# coracao_8bits.net
KiCad netlist of a schematic drawn in EAGLE
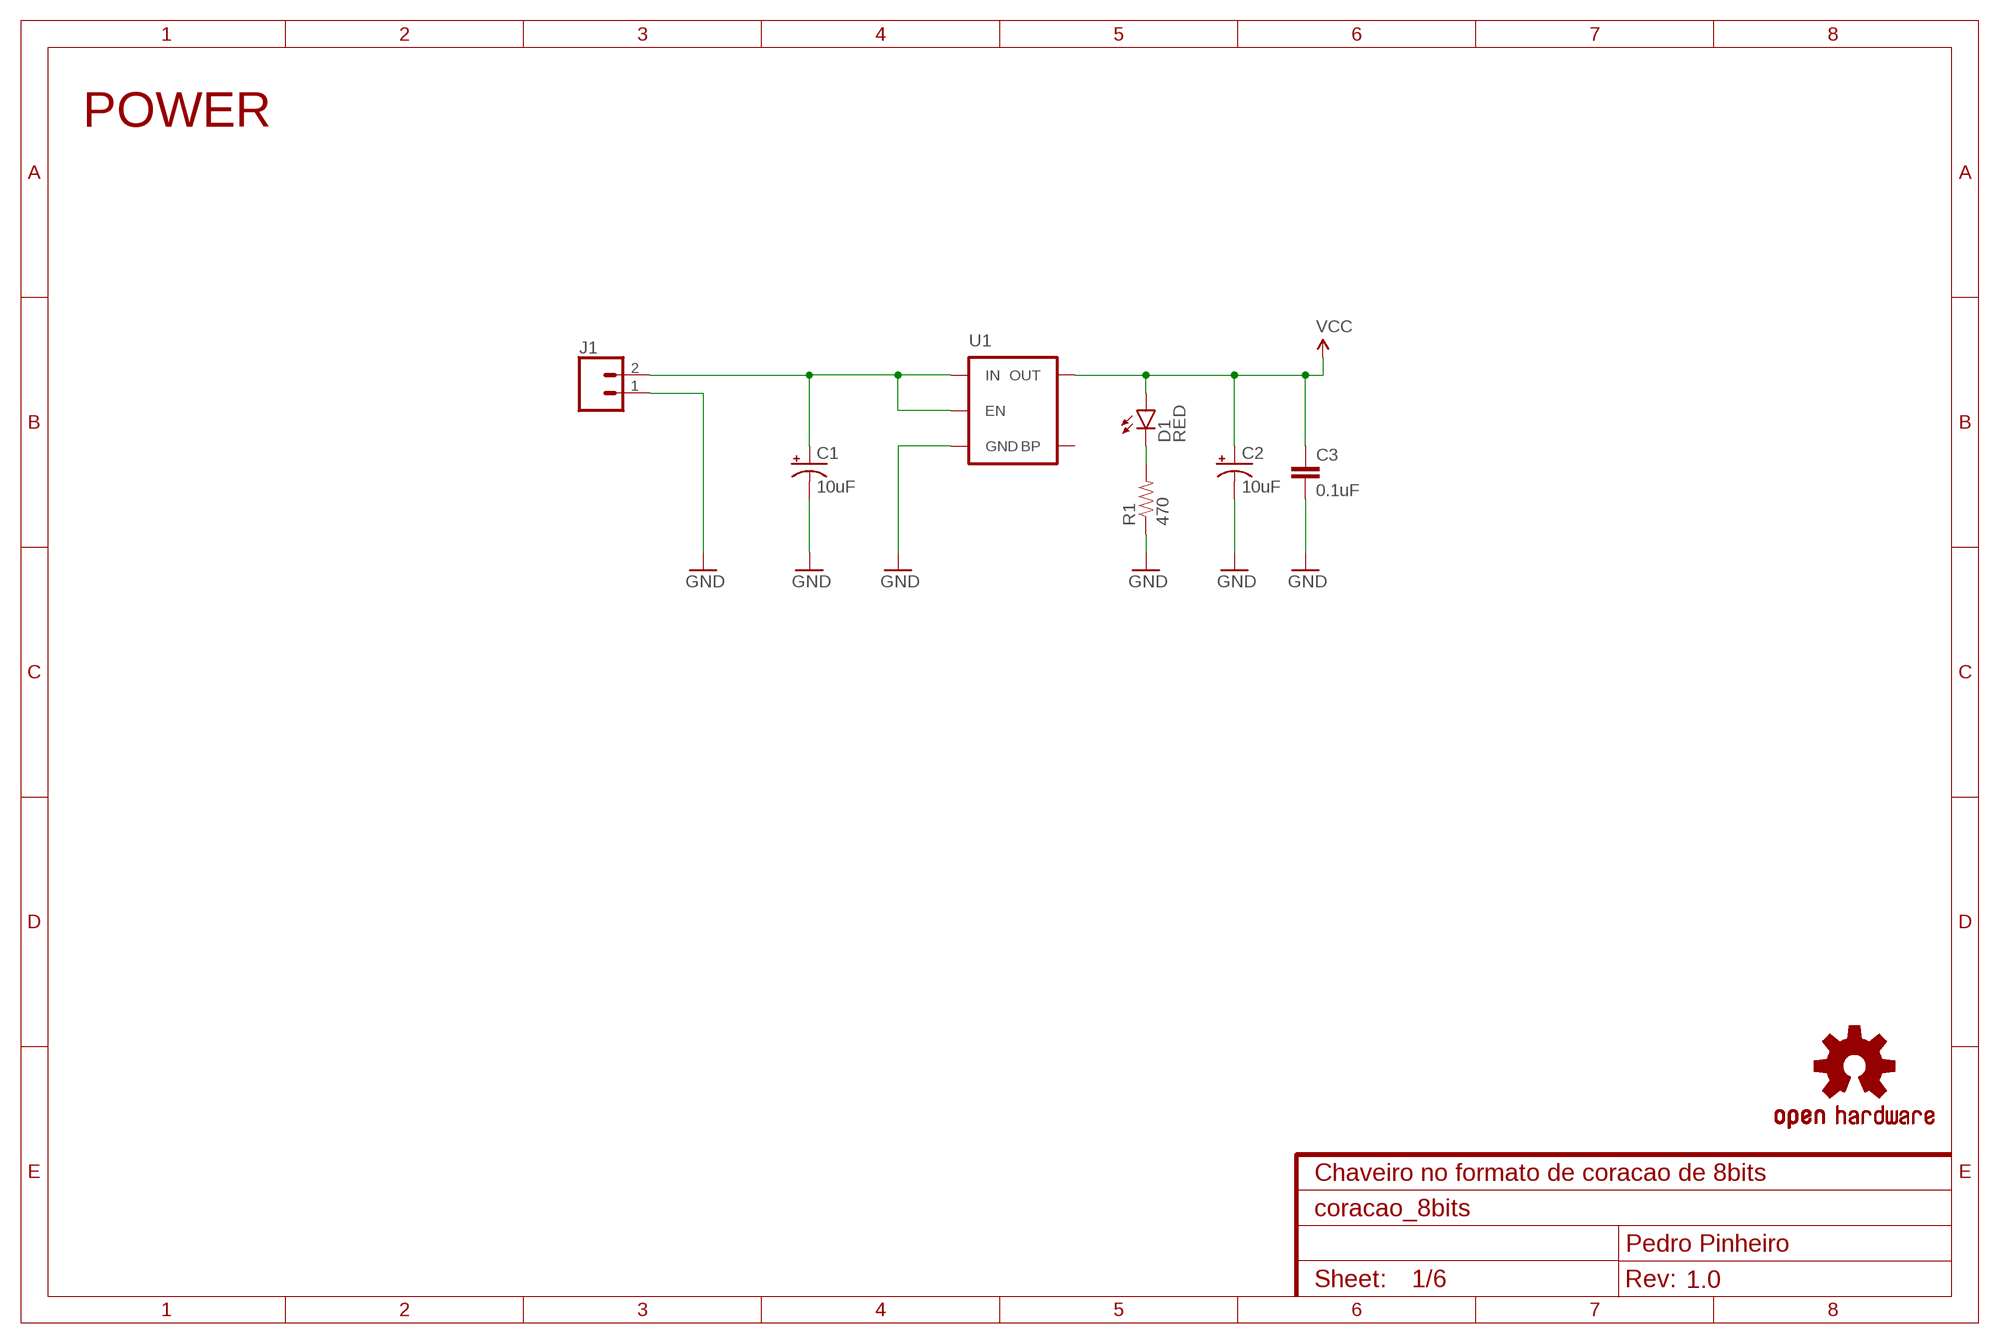
[diagram p0: schematic, sheet 1]
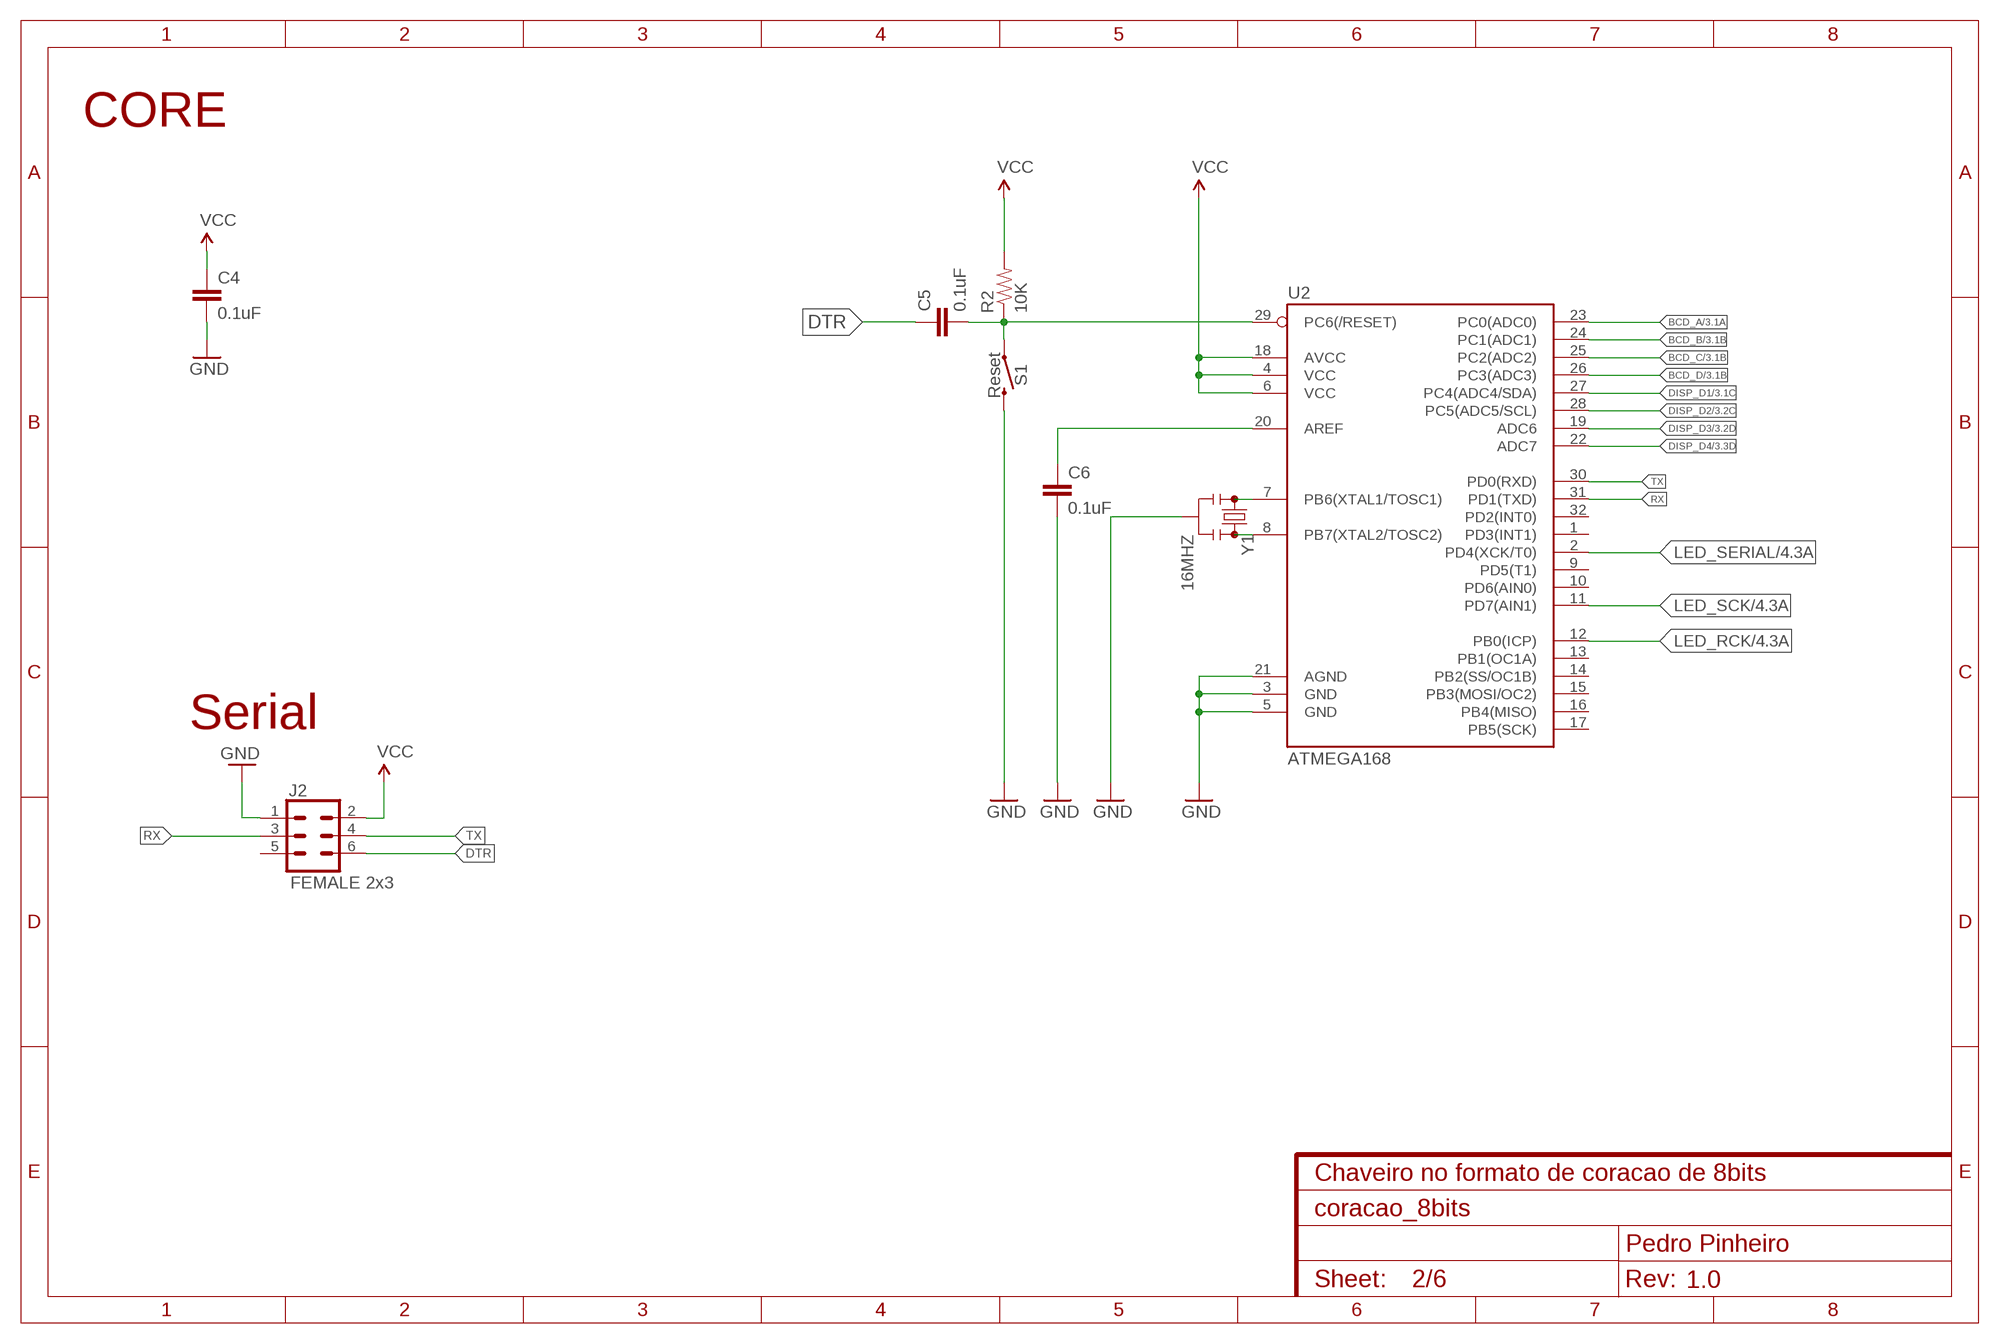
[diagram p1: schematic, sheet 2]
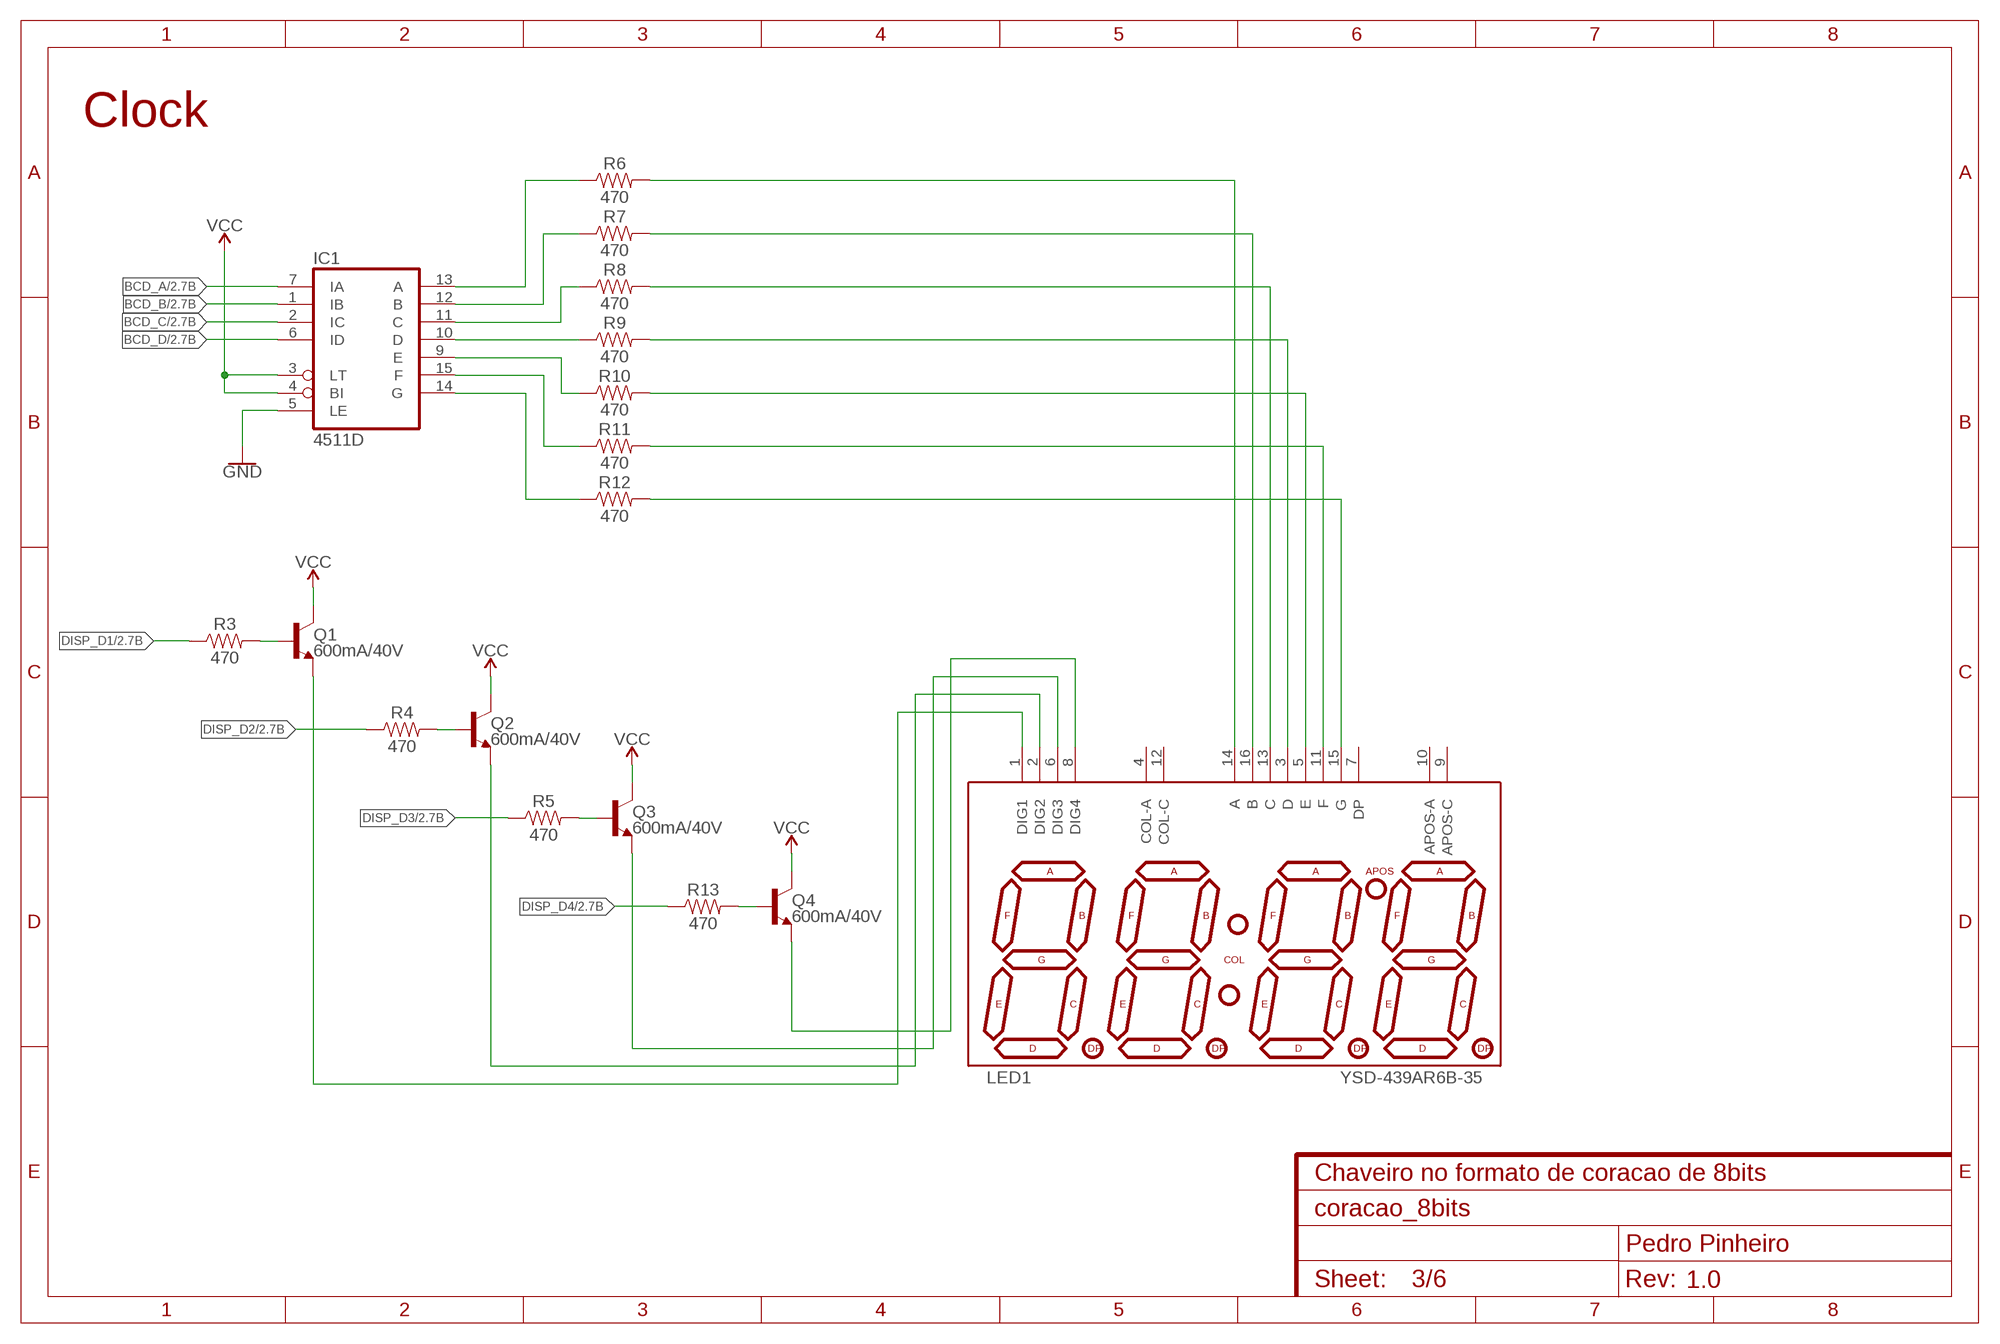
[diagram p2: schematic, sheet 3]
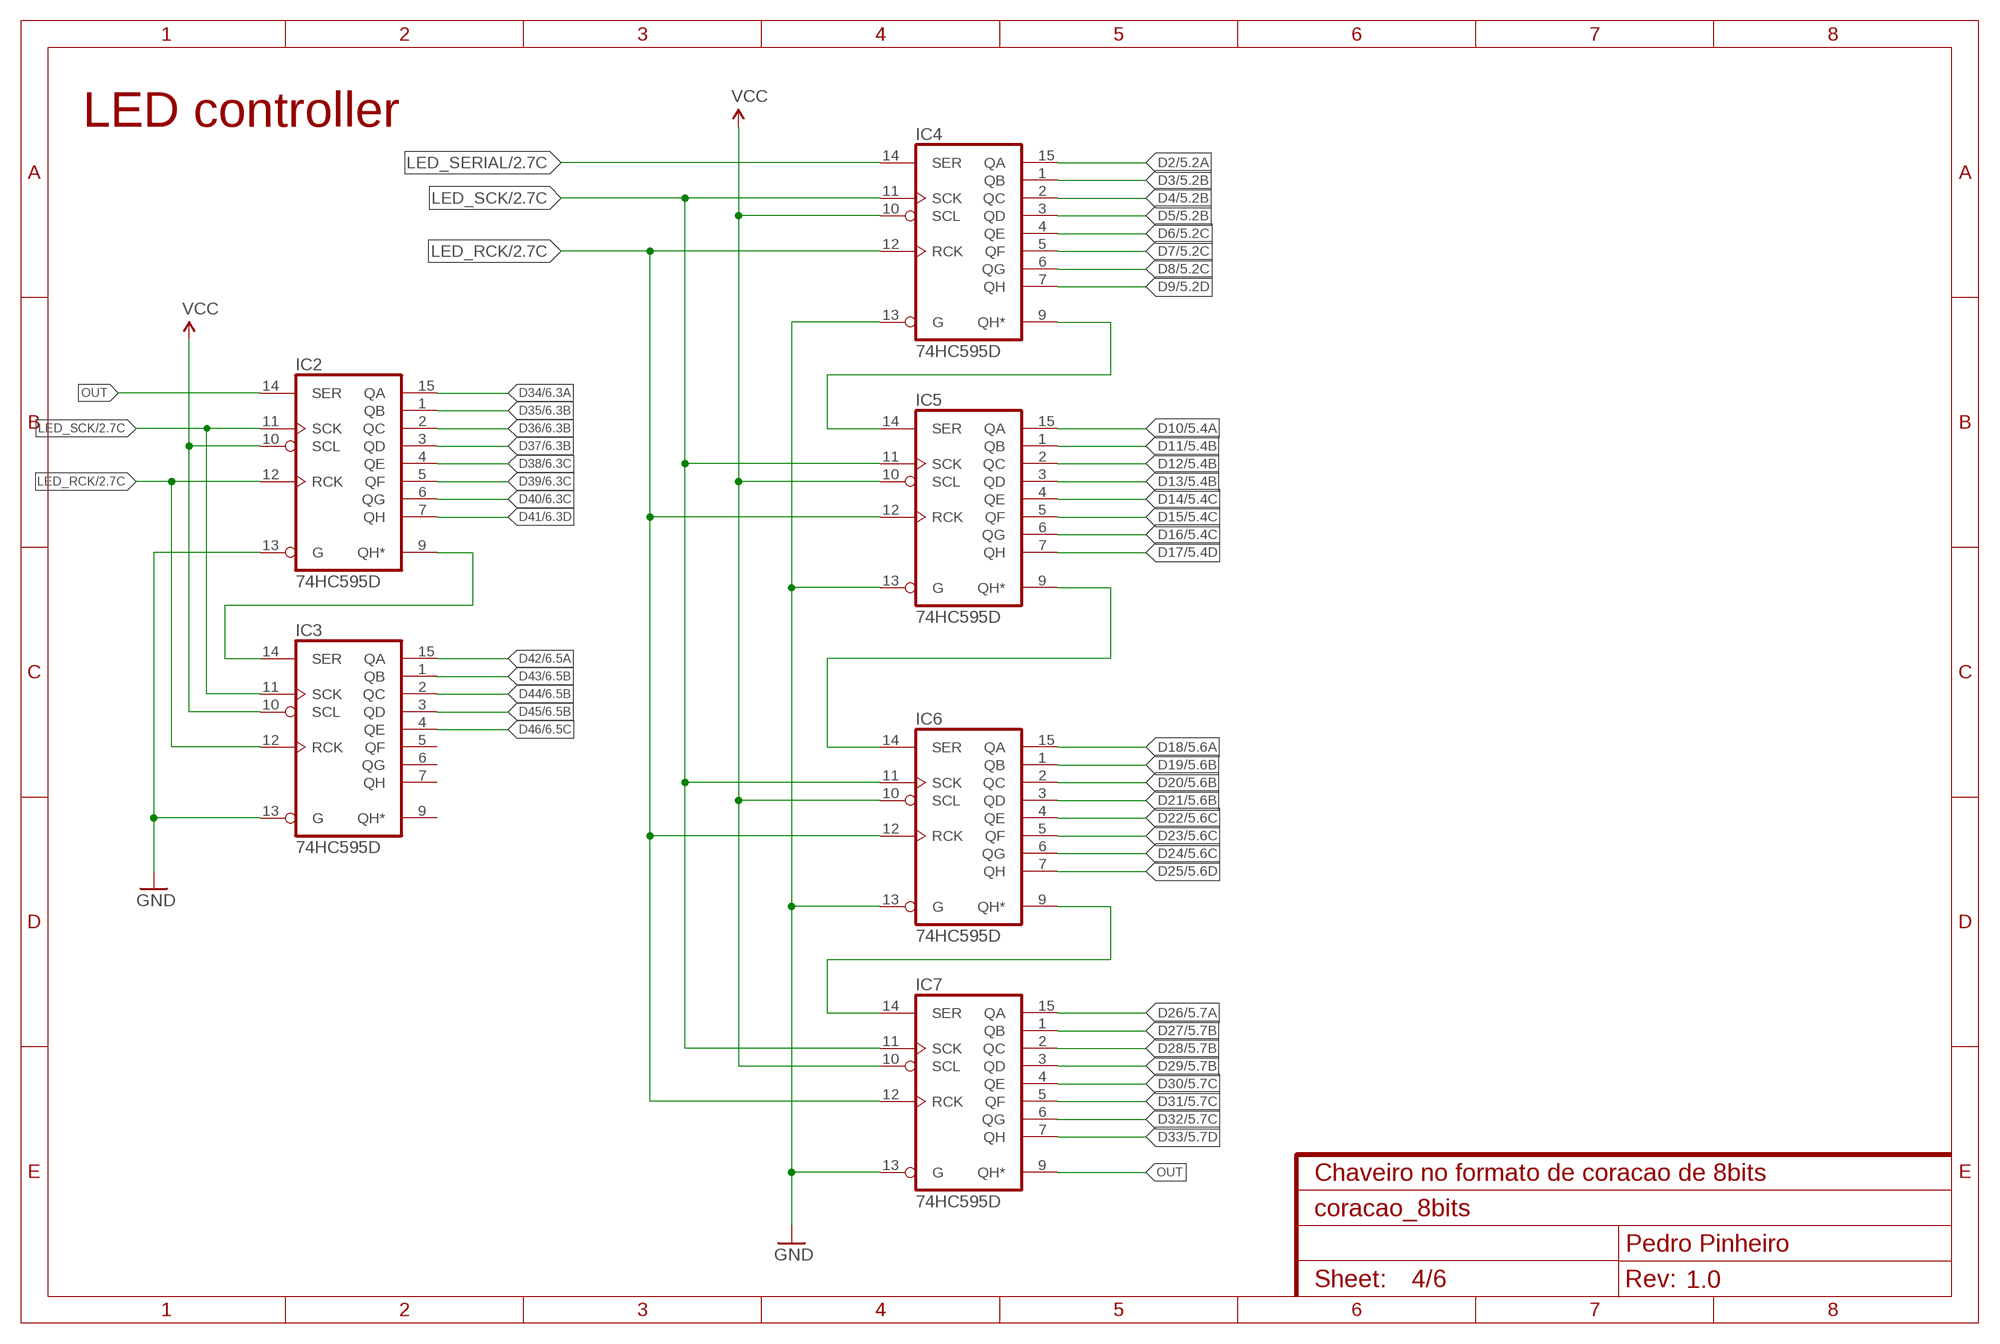
[diagram p3: schematic, sheet 4]
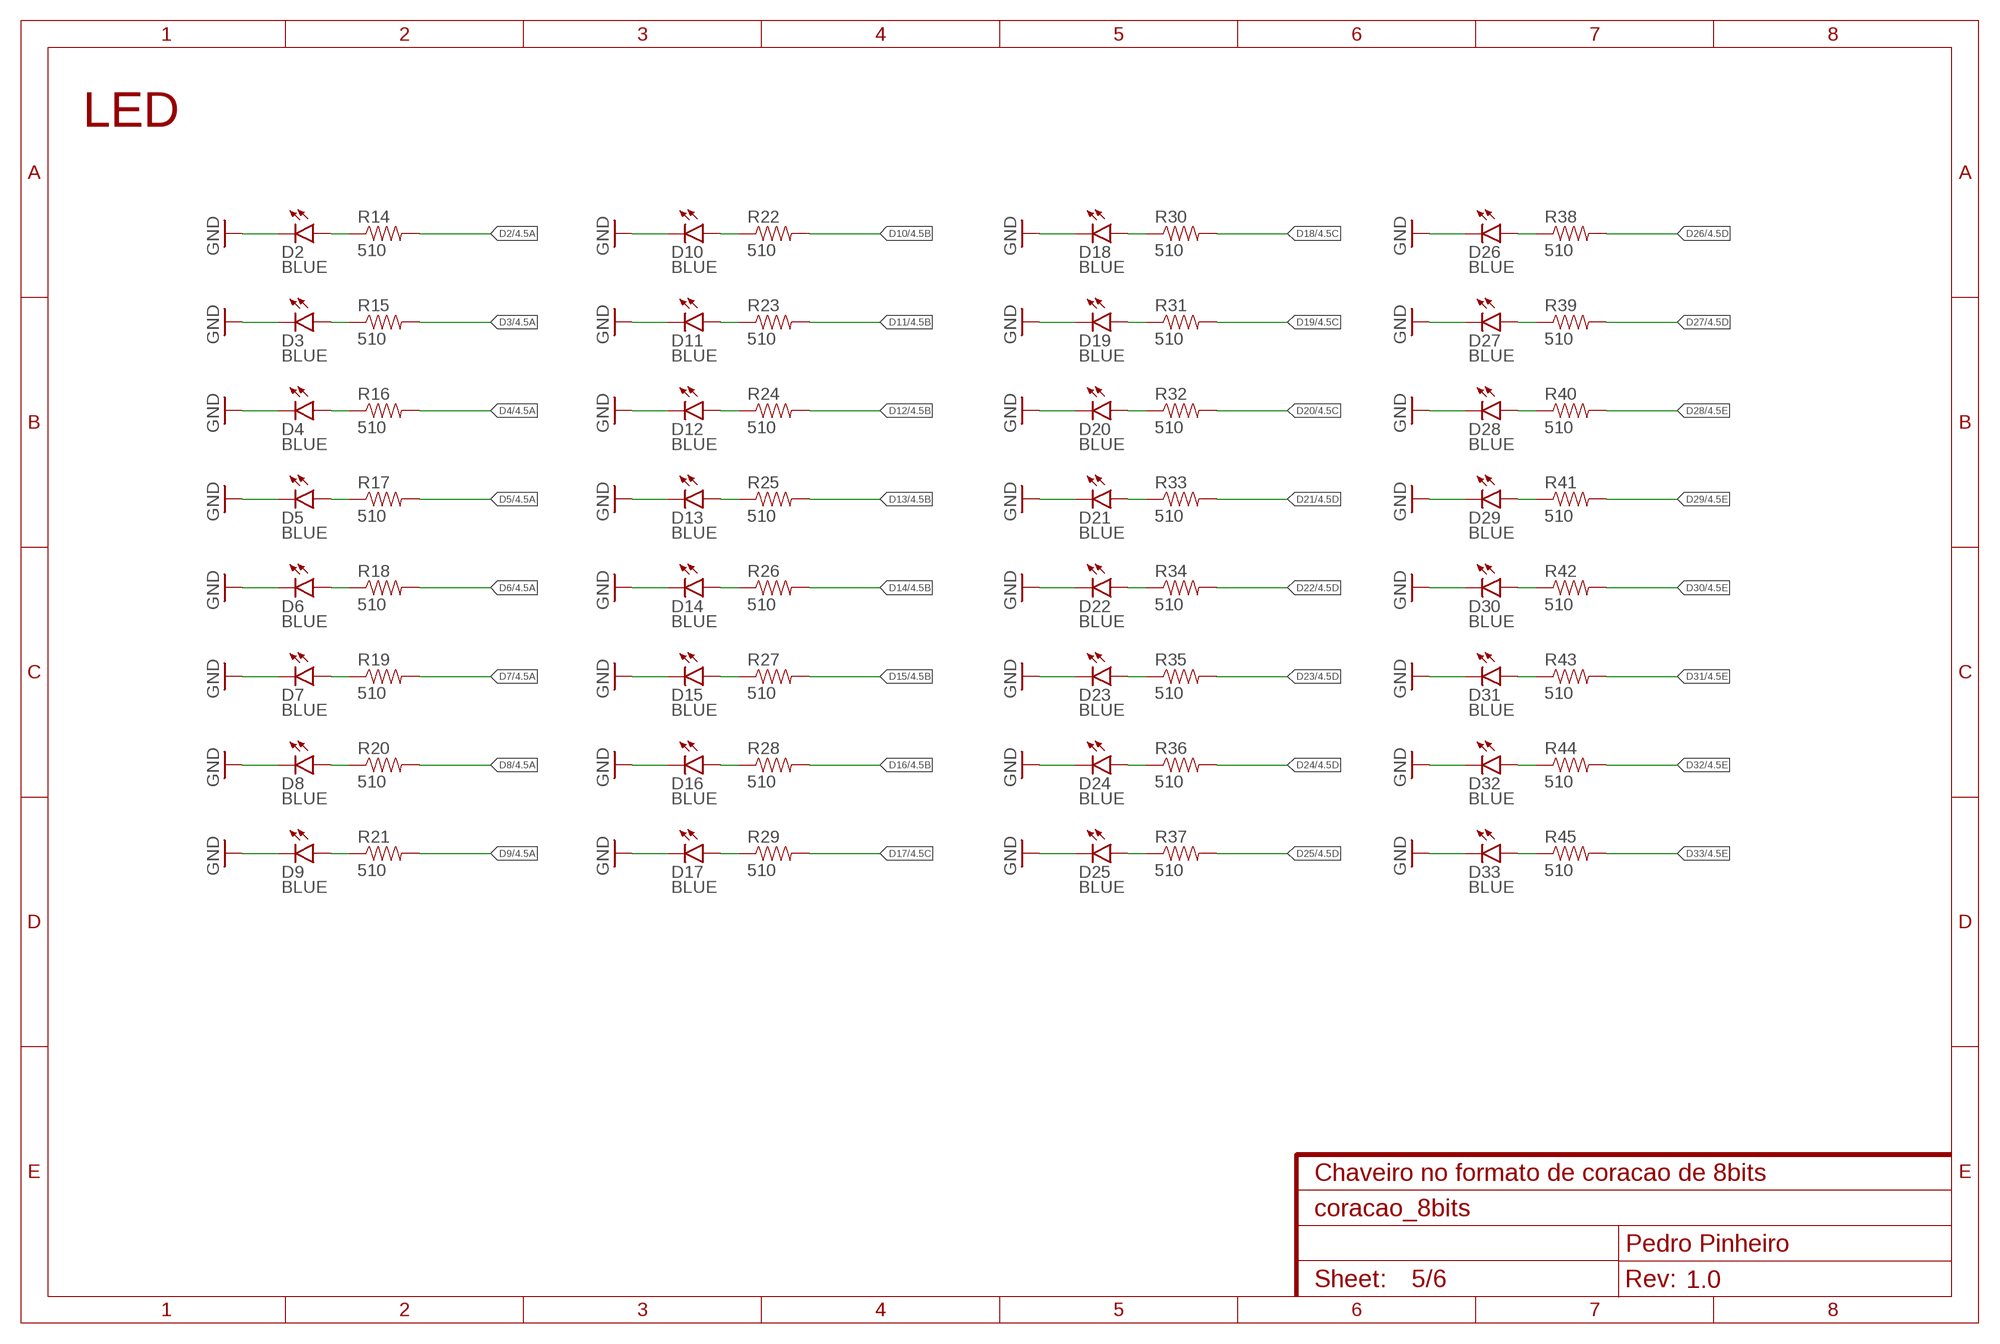
[diagram p4: schematic, sheet 5]
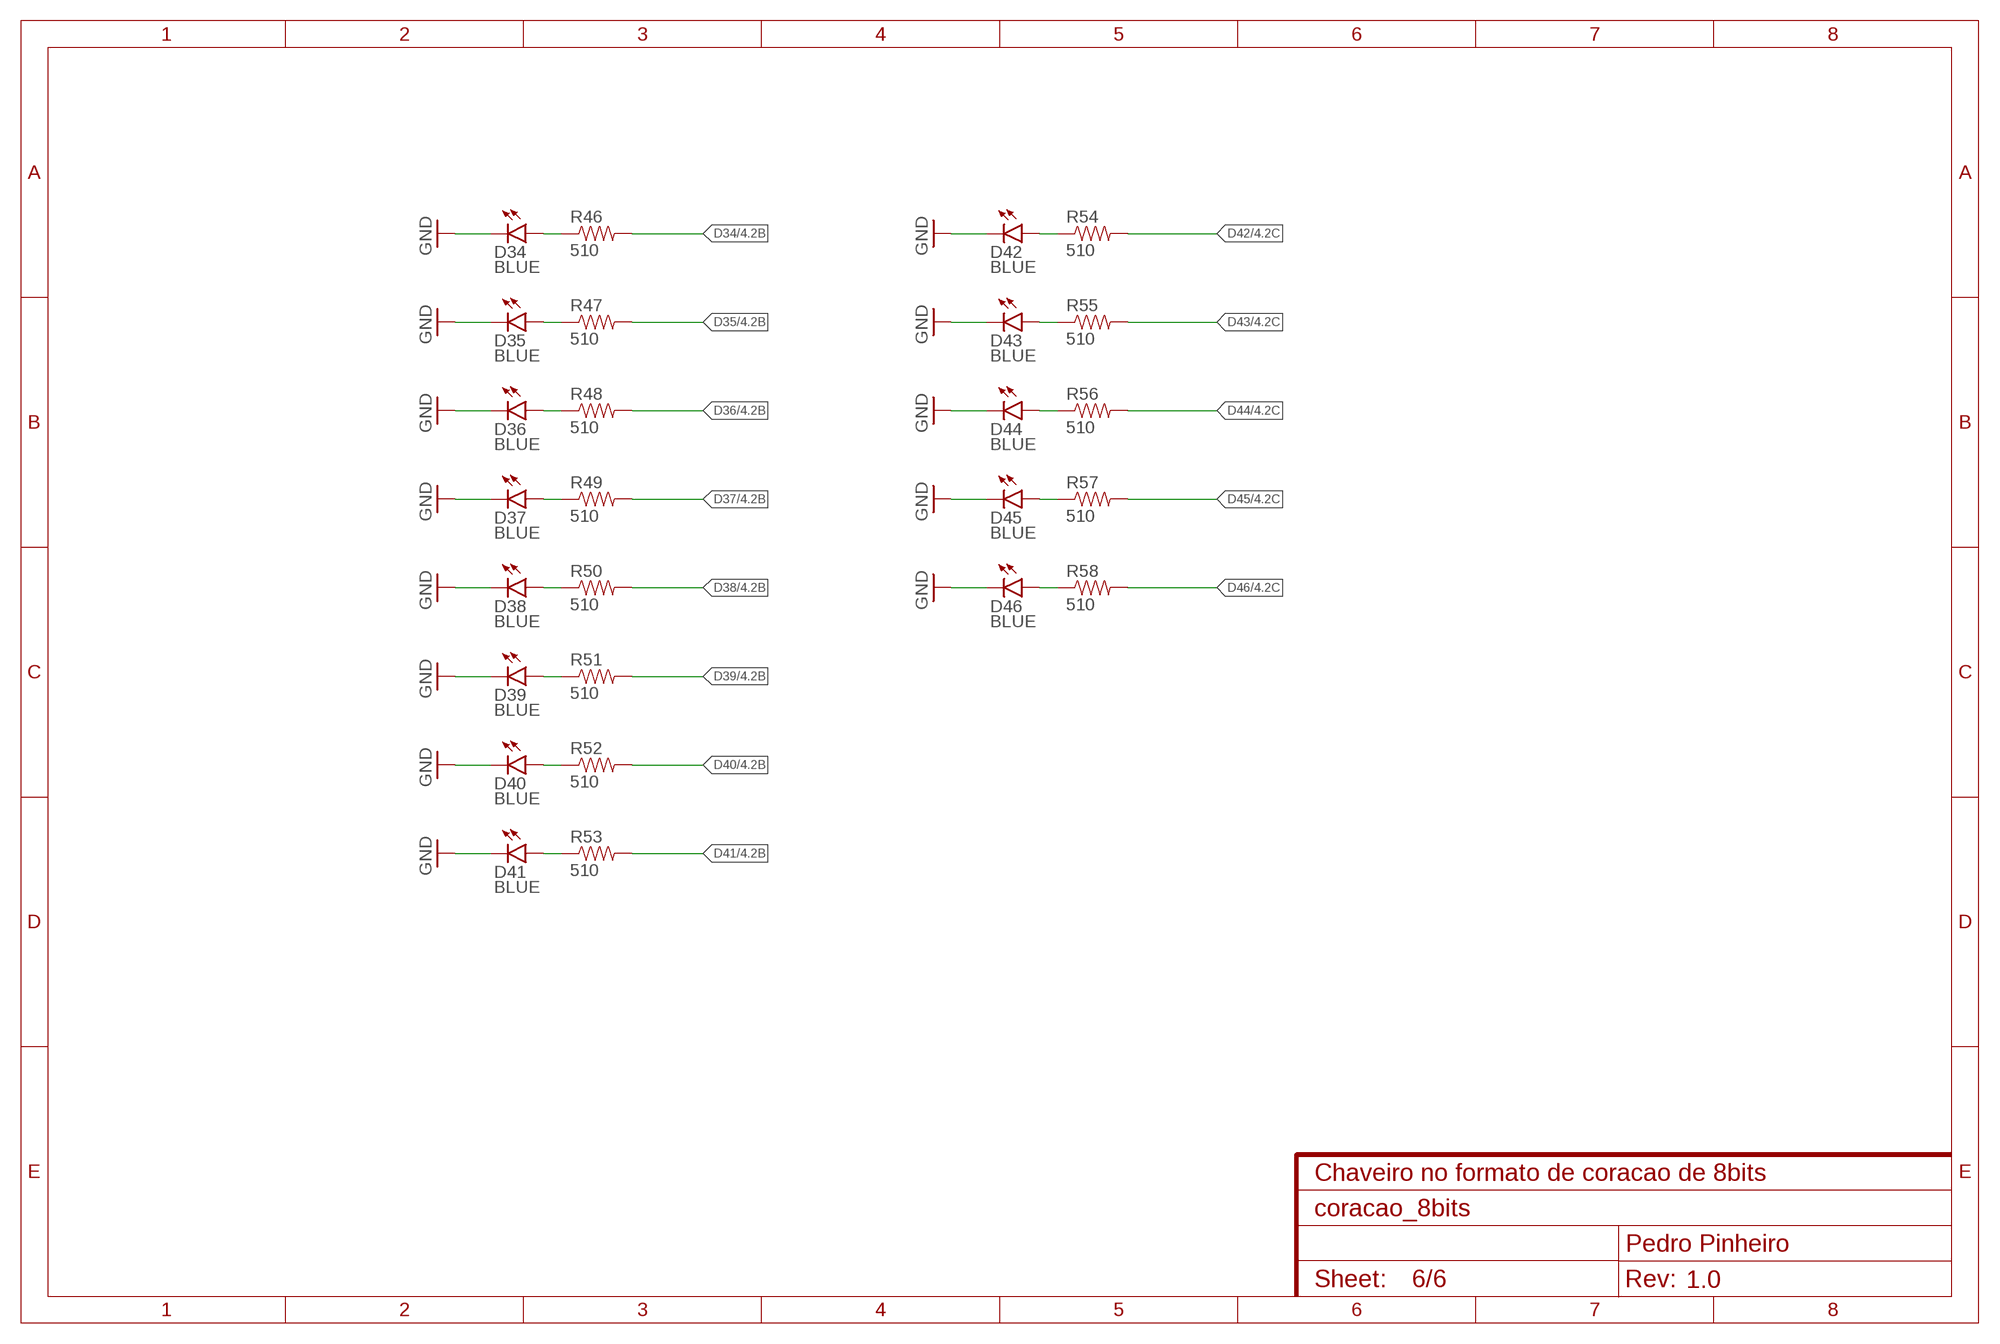
[diagram p5: schematic, sheet 6]

(export (version "E")
  (design (tool "Eeschema 10.0.6"))
  (components
    (comp (ref "IC2")
      (value "74HC595D")
      (footprint "eagle-import:SO16")
      (libsource (lib "eagle-import") (part "74595DHC"))
    )
    (comp (ref "IC3")
      (value "74HC595D")
      (footprint "eagle-import:SO16")
      (libsource (lib "eagle-import") (part "74595DHC"))
    )
    (comp (ref "IC4")
      (value "74HC595D")
      (footprint "eagle-import:SO16")
      (libsource (lib "eagle-import") (part "74595DHC"))
    )
    (comp (ref "IC5")
      (value "74HC595D")
      (footprint "eagle-import:SO16")
      (libsource (lib "eagle-import") (part "74595DHC"))
    )
    (comp (ref "IC6")
      (value "74HC595D")
      (footprint "eagle-import:SO16")
      (libsource (lib "eagle-import") (part "74595DHC"))
    )
    (comp (ref "IC7")
      (value "74HC595D")
      (footprint "eagle-import:SO16")
      (libsource (lib "eagle-import") (part "74595DHC"))
    )
    (comp (ref "C1")
      (value "10uF")
      (footprint "eagle-import:EIA3216")
      (libsource (lib "eagle-import") (part "CAP_POL1206"))
    )
    (comp (ref "C2")
      (value "10uF")
      (footprint "eagle-import:EIA3216")
      (libsource (lib "eagle-import") (part "CAP_POL1206"))
    )
    (comp (ref "C3")
      (value "0.1uF")
      (footprint "eagle-import:0603-CAP")
      (libsource (lib "eagle-import") (part "0.1UF-25V-5%(0603)"))
    )
    (comp (ref "D1")
      (value "RED")
      (footprint "eagle-import:LED-0603")
      (libsource (lib "eagle-import") (part "LED-RED0603"))
    )
    (comp (ref "J1")
      (value "CONN_02")
      (footprint "eagle-import:1X02")
      (libsource (lib "eagle-import") (part "CONN_02"))
    )
    (comp (ref "LOGO1")
      (value "OSHW-LOGOMINI")
      (footprint "eagle-import:OSHW-LOGO-MINI")
      (libsource (lib "eagle-import") (part "OSHW-LOGOMINI"))
    )
    (comp (ref "R1")
      (value "470")
      (footprint "eagle-import:0603-RES")
      (libsource (lib "eagle-import") (part "470OHM1/10W1%(0603)"))
    )
    (comp (ref "U1")
      (value "MIC52053.3V")
      (footprint "eagle-import:SOT23-5")
      (libsource (lib "eagle-import") (part "MIC52053.3V"))
    )
    (comp (ref "IC1")
      (value "4511D")
      (footprint "eagle-import:SO16")
      (libsource (lib "eagle-import") (part "4511D"))
    )
    (comp (ref "LED1")
      (value "YSD-439AR6B-35")
      (footprint "eagle-import:7-SEGMENT-4DIGIT-YOUNGSUN")
      (libsource (lib "eagle-import") (part "7-SEGMENT-4DIGIT-10MM-RED"))
    )
    (comp (ref "Q1")
      (value "600mA/40V")
      (footprint "eagle-import:SOT23-3")
      (libsource (lib "eagle-import") (part "TRANS_NPN-MMBT2222AL"))
    )
    (comp (ref "Q2")
      (value "600mA/40V")
      (footprint "eagle-import:SOT23-3")
      (libsource (lib "eagle-import") (part "TRANS_NPN-MMBT2222AL"))
    )
    (comp (ref "Q3")
      (value "600mA/40V")
      (footprint "eagle-import:SOT23-3")
      (libsource (lib "eagle-import") (part "TRANS_NPN-MMBT2222AL"))
    )
    (comp (ref "Q4")
      (value "600mA/40V")
      (footprint "eagle-import:SOT23-3")
      (libsource (lib "eagle-import") (part "TRANS_NPN-MMBT2222AL"))
    )
    (comp (ref "R3")
      (value "470")
      (footprint "eagle-import:0603")
      (libsource (lib "eagle-import") (part "470OHM-0603-1/10W-1%"))
    )
    (comp (ref "R4")
      (value "470")
      (footprint "eagle-import:0603")
      (libsource (lib "eagle-import") (part "470OHM-0603-1/10W-1%"))
    )
    (comp (ref "R5")
      (value "470")
      (footprint "eagle-import:0603")
      (libsource (lib "eagle-import") (part "470OHM-0603-1/10W-1%"))
    )
    (comp (ref "R6")
      (value "470")
      (footprint "eagle-import:0603")
      (libsource (lib "eagle-import") (part "470OHM-0603-1/10W-1%"))
    )
    (comp (ref "R7")
      (value "470")
      (footprint "eagle-import:0603")
      (libsource (lib "eagle-import") (part "470OHM-0603-1/10W-1%"))
    )
    (comp (ref "R8")
      (value "470")
      (footprint "eagle-import:0603")
      (libsource (lib "eagle-import") (part "470OHM-0603-1/10W-1%"))
    )
    (comp (ref "R9")
      (value "470")
      (footprint "eagle-import:0603")
      (libsource (lib "eagle-import") (part "470OHM-0603-1/10W-1%"))
    )
    (comp (ref "R10")
      (value "470")
      (footprint "eagle-import:0603")
      (libsource (lib "eagle-import") (part "470OHM-0603-1/10W-1%"))
    )
    (comp (ref "R11")
      (value "470")
      (footprint "eagle-import:0603")
      (libsource (lib "eagle-import") (part "470OHM-0603-1/10W-1%"))
    )
    (comp (ref "R12")
      (value "470")
      (footprint "eagle-import:0603")
      (libsource (lib "eagle-import") (part "470OHM-0603-1/10W-1%"))
    )
    (comp (ref "R13")
      (value "470")
      (footprint "eagle-import:0603")
      (libsource (lib "eagle-import") (part "470OHM-0603-1/10W-1%"))
    )
    (comp (ref "C4")
      (value "0.1uF")
      (footprint "eagle-import:0603-CAP")
      (libsource (lib "eagle-import") (part "0.1UF-100V-10%(0603)"))
    )
    (comp (ref "C5")
      (value "0.1uF")
      (footprint "eagle-import:0603-CAP")
      (libsource (lib "eagle-import") (part "0.1UF-100V-10%(0603)"))
    )
    (comp (ref "C6")
      (value "0.1uF")
      (footprint "eagle-import:0603-CAP")
      (libsource (lib "eagle-import") (part "0.1UF-100V-10%(0603)"))
    )
    (comp (ref "J2")
      (value "FEMALE 2x3")
      (footprint "eagle-import:2X3")
      (libsource (lib "eagle-import") (part "CONN_03X2FEMALE"))
    )
    (comp (ref "R2")
      (value "10K")
      (footprint "eagle-import:0603-RES")
      (libsource (lib "eagle-import") (part "10KOHM-1/10W-1%(0603)0603"))
    )
    (comp (ref "S1")
      (value "Reset")
      (footprint "eagle-import:TACTILE_SWITCH_SMD_6.0X3.5MM")
      (libsource (lib "eagle-import") (part "MOMENTARY-SWITCH-SPST-SMD-6.0X3.5MM"))
    )
    (comp (ref "U2")
      (value "ATMEGA168")
      (footprint "eagle-import:TQFP32-08")
      (libsource (lib "eagle-import") (part "ATMEGA168"))
    )
    (comp (ref "Y1")
      (value "16MHZ")
      (footprint "eagle-import:RESONATOR-SMD")
      (libsource (lib "eagle-import") (part "RESONATOR16MHZ"))
    )
    (comp (ref "D34")
      (value "BLUE")
      (footprint "eagle-import:LED-0603")
      (libsource (lib "eagle-import") (part "LED-BLUE0603"))
    )
    (comp (ref "D35")
      (value "BLUE")
      (footprint "eagle-import:LED-0603")
      (libsource (lib "eagle-import") (part "LED-BLUE0603"))
    )
    (comp (ref "D36")
      (value "BLUE")
      (footprint "eagle-import:LED-0603")
      (libsource (lib "eagle-import") (part "LED-BLUE0603"))
    )
    (comp (ref "D37")
      (value "BLUE")
      (footprint "eagle-import:LED-0603")
      (libsource (lib "eagle-import") (part "LED-BLUE0603"))
    )
    (comp (ref "D38")
      (value "BLUE")
      (footprint "eagle-import:LED-0603")
      (libsource (lib "eagle-import") (part "LED-BLUE0603"))
    )
    (comp (ref "D39")
      (value "BLUE")
      (footprint "eagle-import:LED-0603")
      (libsource (lib "eagle-import") (part "LED-BLUE0603"))
    )
    (comp (ref "D40")
      (value "BLUE")
      (footprint "eagle-import:LED-0603")
      (libsource (lib "eagle-import") (part "LED-BLUE0603"))
    )
    (comp (ref "D41")
      (value "BLUE")
      (footprint "eagle-import:LED-0603")
      (libsource (lib "eagle-import") (part "LED-BLUE0603"))
    )
    (comp (ref "D42")
      (value "BLUE")
      (footprint "eagle-import:LED-0603")
      (libsource (lib "eagle-import") (part "LED-BLUE0603"))
    )
    (comp (ref "D43")
      (value "BLUE")
      (footprint "eagle-import:LED-0603")
      (libsource (lib "eagle-import") (part "LED-BLUE0603"))
    )
    (comp (ref "D44")
      (value "BLUE")
      (footprint "eagle-import:LED-0603")
      (libsource (lib "eagle-import") (part "LED-BLUE0603"))
    )
    (comp (ref "D45")
      (value "BLUE")
      (footprint "eagle-import:LED-0603")
      (libsource (lib "eagle-import") (part "LED-BLUE0603"))
    )
    (comp (ref "D46")
      (value "BLUE")
      (footprint "eagle-import:LED-0603")
      (libsource (lib "eagle-import") (part "LED-BLUE0603"))
    )
    (comp (ref "R46")
      (value "510")
      (footprint "eagle-import:0603-RES")
      (libsource (lib "eagle-import") (part "470OHM1/10W1%(0603)"))
    )
    (comp (ref "R47")
      (value "510")
      (footprint "eagle-import:0603-RES")
      (libsource (lib "eagle-import") (part "470OHM1/10W1%(0603)"))
    )
    (comp (ref "R48")
      (value "510")
      (footprint "eagle-import:0603-RES")
      (libsource (lib "eagle-import") (part "470OHM1/10W1%(0603)"))
    )
    (comp (ref "R49")
      (value "510")
      (footprint "eagle-import:0603-RES")
      (libsource (lib "eagle-import") (part "470OHM1/10W1%(0603)"))
    )
    (comp (ref "R50")
      (value "510")
      (footprint "eagle-import:0603-RES")
      (libsource (lib "eagle-import") (part "470OHM1/10W1%(0603)"))
    )
    (comp (ref "R51")
      (value "510")
      (footprint "eagle-import:0603-RES")
      (libsource (lib "eagle-import") (part "470OHM1/10W1%(0603)"))
    )
    (comp (ref "R52")
      (value "510")
      (footprint "eagle-import:0603-RES")
      (libsource (lib "eagle-import") (part "470OHM1/10W1%(0603)"))
    )
    (comp (ref "R53")
      (value "510")
      (footprint "eagle-import:0603-RES")
      (libsource (lib "eagle-import") (part "470OHM1/10W1%(0603)"))
    )
    (comp (ref "R54")
      (value "510")
      (footprint "eagle-import:0603-RES")
      (libsource (lib "eagle-import") (part "470OHM1/10W1%(0603)"))
    )
    (comp (ref "R55")
      (value "510")
      (footprint "eagle-import:0603-RES")
      (libsource (lib "eagle-import") (part "470OHM1/10W1%(0603)"))
    )
    (comp (ref "R56")
      (value "510")
      (footprint "eagle-import:0603-RES")
      (libsource (lib "eagle-import") (part "470OHM1/10W1%(0603)"))
    )
    (comp (ref "R57")
      (value "510")
      (footprint "eagle-import:0603-RES")
      (libsource (lib "eagle-import") (part "470OHM1/10W1%(0603)"))
    )
    (comp (ref "R58")
      (value "510")
      (footprint "eagle-import:0603-RES")
      (libsource (lib "eagle-import") (part "470OHM1/10W1%(0603)"))
    )
    (comp (ref "D2")
      (value "BLUE")
      (footprint "eagle-import:LED-0603")
      (libsource (lib "eagle-import") (part "LED-BLUE0603"))
    )
    (comp (ref "D3")
      (value "BLUE")
      (footprint "eagle-import:LED-0603")
      (libsource (lib "eagle-import") (part "LED-BLUE0603"))
    )
    (comp (ref "D4")
      (value "BLUE")
      (footprint "eagle-import:LED-0603")
      (libsource (lib "eagle-import") (part "LED-BLUE0603"))
    )
    (comp (ref "D5")
      (value "BLUE")
      (footprint "eagle-import:LED-0603")
      (libsource (lib "eagle-import") (part "LED-BLUE0603"))
    )
    (comp (ref "D6")
      (value "BLUE")
      (footprint "eagle-import:LED-0603")
      (libsource (lib "eagle-import") (part "LED-BLUE0603"))
    )
    (comp (ref "D7")
      (value "BLUE")
      (footprint "eagle-import:LED-0603")
      (libsource (lib "eagle-import") (part "LED-BLUE0603"))
    )
    (comp (ref "D8")
      (value "BLUE")
      (footprint "eagle-import:LED-0603")
      (libsource (lib "eagle-import") (part "LED-BLUE0603"))
    )
    (comp (ref "D9")
      (value "BLUE")
      (footprint "eagle-import:LED-0603")
      (libsource (lib "eagle-import") (part "LED-BLUE0603"))
    )
    (comp (ref "D10")
      (value "BLUE")
      (footprint "eagle-import:LED-0603")
      (libsource (lib "eagle-import") (part "LED-BLUE0603"))
    )
    (comp (ref "D11")
      (value "BLUE")
      (footprint "eagle-import:LED-0603")
      (libsource (lib "eagle-import") (part "LED-BLUE0603"))
    )
    (comp (ref "D12")
      (value "BLUE")
      (footprint "eagle-import:LED-0603")
      (libsource (lib "eagle-import") (part "LED-BLUE0603"))
    )
    (comp (ref "D13")
      (value "BLUE")
      (footprint "eagle-import:LED-0603")
      (libsource (lib "eagle-import") (part "LED-BLUE0603"))
    )
    (comp (ref "D14")
      (value "BLUE")
      (footprint "eagle-import:LED-0603")
      (libsource (lib "eagle-import") (part "LED-BLUE0603"))
    )
    (comp (ref "D15")
      (value "BLUE")
      (footprint "eagle-import:LED-0603")
      (libsource (lib "eagle-import") (part "LED-BLUE0603"))
    )
    (comp (ref "D16")
      (value "BLUE")
      (footprint "eagle-import:LED-0603")
      (libsource (lib "eagle-import") (part "LED-BLUE0603"))
    )
    (comp (ref "D17")
      (value "BLUE")
      (footprint "eagle-import:LED-0603")
      (libsource (lib "eagle-import") (part "LED-BLUE0603"))
    )
    (comp (ref "D18")
      (value "BLUE")
      (footprint "eagle-import:LED-0603")
      (libsource (lib "eagle-import") (part "LED-BLUE0603"))
    )
    (comp (ref "D19")
      (value "BLUE")
      (footprint "eagle-import:LED-0603")
      (libsource (lib "eagle-import") (part "LED-BLUE0603"))
    )
    (comp (ref "D20")
      (value "BLUE")
      (footprint "eagle-import:LED-0603")
      (libsource (lib "eagle-import") (part "LED-BLUE0603"))
    )
    (comp (ref "D21")
      (value "BLUE")
      (footprint "eagle-import:LED-0603")
      (libsource (lib "eagle-import") (part "LED-BLUE0603"))
    )
    (comp (ref "D22")
      (value "BLUE")
      (footprint "eagle-import:LED-0603")
      (libsource (lib "eagle-import") (part "LED-BLUE0603"))
    )
    (comp (ref "D23")
      (value "BLUE")
      (footprint "eagle-import:LED-0603")
      (libsource (lib "eagle-import") (part "LED-BLUE0603"))
    )
    (comp (ref "D24")
      (value "BLUE")
      (footprint "eagle-import:LED-0603")
      (libsource (lib "eagle-import") (part "LED-BLUE0603"))
    )
    (comp (ref "D25")
      (value "BLUE")
      (footprint "eagle-import:LED-0603")
      (libsource (lib "eagle-import") (part "LED-BLUE0603"))
    )
    (comp (ref "D26")
      (value "BLUE")
      (footprint "eagle-import:LED-0603")
      (libsource (lib "eagle-import") (part "LED-BLUE0603"))
    )
    (comp (ref "D27")
      (value "BLUE")
      (footprint "eagle-import:LED-0603")
      (libsource (lib "eagle-import") (part "LED-BLUE0603"))
    )
    (comp (ref "D28")
      (value "BLUE")
      (footprint "eagle-import:LED-0603")
      (libsource (lib "eagle-import") (part "LED-BLUE0603"))
    )
    (comp (ref "D29")
      (value "BLUE")
      (footprint "eagle-import:LED-0603")
      (libsource (lib "eagle-import") (part "LED-BLUE0603"))
    )
    (comp (ref "D30")
      (value "BLUE")
      (footprint "eagle-import:LED-0603")
      (libsource (lib "eagle-import") (part "LED-BLUE0603"))
    )
    (comp (ref "D31")
      (value "BLUE")
      (footprint "eagle-import:LED-0603")
      (libsource (lib "eagle-import") (part "LED-BLUE0603"))
    )
    (comp (ref "D32")
      (value "BLUE")
      (footprint "eagle-import:LED-0603")
      (libsource (lib "eagle-import") (part "LED-BLUE0603"))
    )
    (comp (ref "D33")
      (value "BLUE")
      (footprint "eagle-import:LED-0603")
      (libsource (lib "eagle-import") (part "LED-BLUE0603"))
    )
    (comp (ref "R14")
      (value "510")
      (footprint "eagle-import:0603-RES")
      (libsource (lib "eagle-import") (part "470OHM1/10W1%(0603)"))
    )
    (comp (ref "R15")
      (value "510")
      (footprint "eagle-import:0603-RES")
      (libsource (lib "eagle-import") (part "470OHM1/10W1%(0603)"))
    )
    (comp (ref "R16")
      (value "510")
      (footprint "eagle-import:0603-RES")
      (libsource (lib "eagle-import") (part "470OHM1/10W1%(0603)"))
    )
    (comp (ref "R17")
      (value "510")
      (footprint "eagle-import:0603-RES")
      (libsource (lib "eagle-import") (part "470OHM1/10W1%(0603)"))
    )
    (comp (ref "R18")
      (value "510")
      (footprint "eagle-import:0603-RES")
      (libsource (lib "eagle-import") (part "470OHM1/10W1%(0603)"))
    )
    (comp (ref "R19")
      (value "510")
      (footprint "eagle-import:0603-RES")
      (libsource (lib "eagle-import") (part "470OHM1/10W1%(0603)"))
    )
    (comp (ref "R20")
      (value "510")
      (footprint "eagle-import:0603-RES")
      (libsource (lib "eagle-import") (part "470OHM1/10W1%(0603)"))
    )
    (comp (ref "R21")
      (value "510")
      (footprint "eagle-import:0603-RES")
      (libsource (lib "eagle-import") (part "470OHM1/10W1%(0603)"))
    )
    (comp (ref "R22")
      (value "510")
      (footprint "eagle-import:0603-RES")
      (libsource (lib "eagle-import") (part "470OHM1/10W1%(0603)"))
    )
    (comp (ref "R23")
      (value "510")
      (footprint "eagle-import:0603-RES")
      (libsource (lib "eagle-import") (part "470OHM1/10W1%(0603)"))
    )
    (comp (ref "R24")
      (value "510")
      (footprint "eagle-import:0603-RES")
      (libsource (lib "eagle-import") (part "470OHM1/10W1%(0603)"))
    )
    (comp (ref "R25")
      (value "510")
      (footprint "eagle-import:0603-RES")
      (libsource (lib "eagle-import") (part "470OHM1/10W1%(0603)"))
    )
    (comp (ref "R26")
      (value "510")
      (footprint "eagle-import:0603-RES")
      (libsource (lib "eagle-import") (part "470OHM1/10W1%(0603)"))
    )
    (comp (ref "R27")
      (value "510")
      (footprint "eagle-import:0603-RES")
      (libsource (lib "eagle-import") (part "470OHM1/10W1%(0603)"))
    )
    (comp (ref "R28")
      (value "510")
      (footprint "eagle-import:0603-RES")
      (libsource (lib "eagle-import") (part "470OHM1/10W1%(0603)"))
    )
    (comp (ref "R29")
      (value "510")
      (footprint "eagle-import:0603-RES")
      (libsource (lib "eagle-import") (part "470OHM1/10W1%(0603)"))
    )
    (comp (ref "R30")
      (value "510")
      (footprint "eagle-import:0603-RES")
      (libsource (lib "eagle-import") (part "470OHM1/10W1%(0603)"))
    )
    (comp (ref "R31")
      (value "510")
      (footprint "eagle-import:0603-RES")
      (libsource (lib "eagle-import") (part "470OHM1/10W1%(0603)"))
    )
    (comp (ref "R32")
      (value "510")
      (footprint "eagle-import:0603-RES")
      (libsource (lib "eagle-import") (part "470OHM1/10W1%(0603)"))
    )
    (comp (ref "R33")
      (value "510")
      (footprint "eagle-import:0603-RES")
      (libsource (lib "eagle-import") (part "470OHM1/10W1%(0603)"))
    )
    (comp (ref "R34")
      (value "510")
      (footprint "eagle-import:0603-RES")
      (libsource (lib "eagle-import") (part "470OHM1/10W1%(0603)"))
    )
    (comp (ref "R35")
      (value "510")
      (footprint "eagle-import:0603-RES")
      (libsource (lib "eagle-import") (part "470OHM1/10W1%(0603)"))
    )
    (comp (ref "R36")
      (value "510")
      (footprint "eagle-import:0603-RES")
      (libsource (lib "eagle-import") (part "470OHM1/10W1%(0603)"))
    )
    (comp (ref "R37")
      (value "510")
      (footprint "eagle-import:0603-RES")
      (libsource (lib "eagle-import") (part "470OHM1/10W1%(0603)"))
    )
    (comp (ref "R38")
      (value "510")
      (footprint "eagle-import:0603-RES")
      (libsource (lib "eagle-import") (part "470OHM1/10W1%(0603)"))
    )
    (comp (ref "R39")
      (value "510")
      (footprint "eagle-import:0603-RES")
      (libsource (lib "eagle-import") (part "470OHM1/10W1%(0603)"))
    )
    (comp (ref "R40")
      (value "510")
      (footprint "eagle-import:0603-RES")
      (libsource (lib "eagle-import") (part "470OHM1/10W1%(0603)"))
    )
    (comp (ref "R41")
      (value "510")
      (footprint "eagle-import:0603-RES")
      (libsource (lib "eagle-import") (part "470OHM1/10W1%(0603)"))
    )
    (comp (ref "R42")
      (value "510")
      (footprint "eagle-import:0603-RES")
      (libsource (lib "eagle-import") (part "470OHM1/10W1%(0603)"))
    )
    (comp (ref "R43")
      (value "510")
      (footprint "eagle-import:0603-RES")
      (libsource (lib "eagle-import") (part "470OHM1/10W1%(0603)"))
    )
    (comp (ref "R44")
      (value "510")
      (footprint "eagle-import:0603-RES")
      (libsource (lib "eagle-import") (part "470OHM1/10W1%(0603)"))
    )
    (comp (ref "R45")
      (value "510")
      (footprint "eagle-import:0603-RES")
      (libsource (lib "eagle-import") (part "470OHM1/10W1%(0603)"))
    )
  )
  (nets
    (net (code "1") (name "BCD_A") (class "Default")
      (node (ref "IC1") (pin "7") (pinfunction "IA_7") (pintype "input"))
      (node (ref "U2") (pin "23") (pinfunction "PC0(ADC0)_23") (pintype "bidirectional"))
    )
    (net (code "2") (name "BCD_B") (class "Default")
      (node (ref "IC1") (pin "1") (pinfunction "IB_1") (pintype "input"))
      (node (ref "U2") (pin "24") (pinfunction "PC1(ADC1)_24") (pintype "bidirectional"))
    )
    (net (code "3") (name "BCD_C") (class "Default")
      (node (ref "IC1") (pin "2") (pinfunction "IC_2") (pintype "input"))
      (node (ref "U2") (pin "25") (pinfunction "PC2(ADC2)_25") (pintype "bidirectional"))
    )
    (net (code "4") (name "BCD_D") (class "Default")
      (node (ref "IC1") (pin "6") (pinfunction "ID_6") (pintype "input"))
      (node (ref "U2") (pin "26") (pinfunction "PC3(ADC3)_26") (pintype "bidirectional"))
    )
    (net (code "5") (name "D2") (class "Default")
      (node (ref "IC4") (pin "15") (pinfunction "QA_15") (pintype "tri_state"))
      (node (ref "R14") (pin "2") (pinfunction "2_2") (pintype "passive"))
    )
    (net (code "6") (name "D3") (class "Default")
      (node (ref "IC4") (pin "1") (pinfunction "QB_1") (pintype "tri_state"))
      (node (ref "R15") (pin "2") (pinfunction "2_2") (pintype "passive"))
    )
    (net (code "7") (name "D4") (class "Default")
      (node (ref "IC4") (pin "2") (pinfunction "QC_2") (pintype "tri_state"))
      (node (ref "R16") (pin "2") (pinfunction "2_2") (pintype "passive"))
    )
    (net (code "8") (name "D5") (class "Default")
      (node (ref "IC4") (pin "3") (pinfunction "QD_3") (pintype "tri_state"))
      (node (ref "R17") (pin "2") (pinfunction "2_2") (pintype "passive"))
    )
    (net (code "9") (name "D6") (class "Default")
      (node (ref "IC4") (pin "4") (pinfunction "QE_4") (pintype "tri_state"))
      (node (ref "R18") (pin "2") (pinfunction "2_2") (pintype "passive"))
    )
    (net (code "10") (name "D7") (class "Default")
      (node (ref "IC4") (pin "5") (pinfunction "QF_5") (pintype "tri_state"))
      (node (ref "R19") (pin "2") (pinfunction "2_2") (pintype "passive"))
    )
    (net (code "11") (name "D8") (class "Default")
      (node (ref "IC4") (pin "6") (pinfunction "QG_6") (pintype "tri_state"))
      (node (ref "R20") (pin "2") (pinfunction "2_2") (pintype "passive"))
    )
    (net (code "12") (name "D9") (class "Default")
      (node (ref "IC4") (pin "7") (pinfunction "QH_7") (pintype "tri_state"))
      (node (ref "R21") (pin "2") (pinfunction "2_2") (pintype "passive"))
    )
    (net (code "13") (name "D10") (class "Default")
      (node (ref "IC5") (pin "15") (pinfunction "QA_15") (pintype "tri_state"))
      (node (ref "R22") (pin "2") (pinfunction "2_2") (pintype "passive"))
    )
    (net (code "14") (name "D11") (class "Default")
      (node (ref "IC5") (pin "1") (pinfunction "QB_1") (pintype "tri_state"))
      (node (ref "R23") (pin "2") (pinfunction "2_2") (pintype "passive"))
    )
    (net (code "15") (name "D12") (class "Default")
      (node (ref "IC5") (pin "2") (pinfunction "QC_2") (pintype "tri_state"))
      (node (ref "R24") (pin "2") (pinfunction "2_2") (pintype "passive"))
    )
    (net (code "16") (name "D13") (class "Default")
      (node (ref "IC5") (pin "3") (pinfunction "QD_3") (pintype "tri_state"))
      (node (ref "R25") (pin "2") (pinfunction "2_2") (pintype "passive"))
    )
    (net (code "17") (name "D14") (class "Default")
      (node (ref "IC5") (pin "4") (pinfunction "QE_4") (pintype "tri_state"))
      (node (ref "R26") (pin "2") (pinfunction "2_2") (pintype "passive"))
    )
    (net (code "18") (name "D15") (class "Default")
      (node (ref "IC5") (pin "5") (pinfunction "QF_5") (pintype "tri_state"))
      (node (ref "R27") (pin "2") (pinfunction "2_2") (pintype "passive"))
    )
    (net (code "19") (name "D16") (class "Default")
      (node (ref "IC5") (pin "6") (pinfunction "QG_6") (pintype "tri_state"))
      (node (ref "R28") (pin "2") (pinfunction "2_2") (pintype "passive"))
    )
    (net (code "20") (name "D17") (class "Default")
      (node (ref "IC5") (pin "7") (pinfunction "QH_7") (pintype "tri_state"))
      (node (ref "R29") (pin "2") (pinfunction "2_2") (pintype "passive"))
    )
    (net (code "21") (name "D18") (class "Default")
      (node (ref "IC6") (pin "15") (pinfunction "QA_15") (pintype "tri_state"))
      (node (ref "R30") (pin "2") (pinfunction "2_2") (pintype "passive"))
    )
    (net (code "22") (name "D19") (class "Default")
      (node (ref "IC6") (pin "1") (pinfunction "QB_1") (pintype "tri_state"))
      (node (ref "R31") (pin "2") (pinfunction "2_2") (pintype "passive"))
    )
    (net (code "23") (name "D20") (class "Default")
      (node (ref "IC6") (pin "2") (pinfunction "QC_2") (pintype "tri_state"))
      (node (ref "R32") (pin "2") (pinfunction "2_2") (pintype "passive"))
    )
    (net (code "24") (name "D21") (class "Default")
      (node (ref "IC6") (pin "3") (pinfunction "QD_3") (pintype "tri_state"))
      (node (ref "R33") (pin "2") (pinfunction "2_2") (pintype "passive"))
    )
    (net (code "25") (name "D22") (class "Default")
      (node (ref "IC6") (pin "4") (pinfunction "QE_4") (pintype "tri_state"))
      (node (ref "R34") (pin "2") (pinfunction "2_2") (pintype "passive"))
    )
    (net (code "26") (name "D23") (class "Default")
      (node (ref "IC6") (pin "5") (pinfunction "QF_5") (pintype "tri_state"))
      (node (ref "R35") (pin "2") (pinfunction "2_2") (pintype "passive"))
    )
    (net (code "27") (name "D24") (class "Default")
      (node (ref "IC6") (pin "6") (pinfunction "QG_6") (pintype "tri_state"))
      (node (ref "R36") (pin "2") (pinfunction "2_2") (pintype "passive"))
    )
    (net (code "28") (name "D25") (class "Default")
      (node (ref "IC6") (pin "7") (pinfunction "QH_7") (pintype "tri_state"))
      (node (ref "R37") (pin "2") (pinfunction "2_2") (pintype "passive"))
    )
    (net (code "29") (name "D26") (class "Default")
      (node (ref "IC7") (pin "15") (pinfunction "QA_15") (pintype "tri_state"))
      (node (ref "R38") (pin "2") (pinfunction "2_2") (pintype "passive"))
    )
    (net (code "30") (name "D27") (class "Default")
      (node (ref "IC7") (pin "1") (pinfunction "QB_1") (pintype "tri_state"))
      (node (ref "R39") (pin "2") (pinfunction "2_2") (pintype "passive"))
    )
    (net (code "31") (name "D28") (class "Default")
      (node (ref "IC7") (pin "2") (pinfunction "QC_2") (pintype "tri_state"))
      (node (ref "R40") (pin "2") (pinfunction "2_2") (pintype "passive"))
    )
    (net (code "32") (name "D29") (class "Default")
      (node (ref "IC7") (pin "3") (pinfunction "QD_3") (pintype "tri_state"))
      (node (ref "R41") (pin "2") (pinfunction "2_2") (pintype "passive"))
    )
    (net (code "33") (name "D30") (class "Default")
      (node (ref "IC7") (pin "4") (pinfunction "QE_4") (pintype "tri_state"))
      (node (ref "R42") (pin "2") (pinfunction "2_2") (pintype "passive"))
    )
    (net (code "34") (name "D31") (class "Default")
      (node (ref "IC7") (pin "5") (pinfunction "QF_5") (pintype "tri_state"))
      (node (ref "R43") (pin "2") (pinfunction "2_2") (pintype "passive"))
    )
    (net (code "35") (name "D32") (class "Default")
      (node (ref "IC7") (pin "6") (pinfunction "QG_6") (pintype "tri_state"))
      (node (ref "R44") (pin "2") (pinfunction "2_2") (pintype "passive"))
    )
    (net (code "36") (name "D33") (class "Default")
      (node (ref "IC7") (pin "7") (pinfunction "QH_7") (pintype "tri_state"))
      (node (ref "R45") (pin "2") (pinfunction "2_2") (pintype "passive"))
    )
    (net (code "37") (name "D34") (class "Default")
      (node (ref "IC2") (pin "15") (pinfunction "QA_15") (pintype "tri_state"))
      (node (ref "R46") (pin "2") (pinfunction "2_2") (pintype "passive"))
    )
    (net (code "38") (name "D35") (class "Default")
      (node (ref "IC2") (pin "1") (pinfunction "QB_1") (pintype "tri_state"))
      (node (ref "R47") (pin "2") (pinfunction "2_2") (pintype "passive"))
    )
    (net (code "39") (name "D36") (class "Default")
      (node (ref "IC2") (pin "2") (pinfunction "QC_2") (pintype "tri_state"))
      (node (ref "R48") (pin "2") (pinfunction "2_2") (pintype "passive"))
    )
    (net (code "40") (name "D37") (class "Default")
      (node (ref "IC2") (pin "3") (pinfunction "QD_3") (pintype "tri_state"))
      (node (ref "R49") (pin "2") (pinfunction "2_2") (pintype "passive"))
    )
    (net (code "41") (name "D38") (class "Default")
      (node (ref "IC2") (pin "4") (pinfunction "QE_4") (pintype "tri_state"))
      (node (ref "R50") (pin "2") (pinfunction "2_2") (pintype "passive"))
    )
    (net (code "42") (name "D39") (class "Default")
      (node (ref "IC2") (pin "5") (pinfunction "QF_5") (pintype "tri_state"))
      (node (ref "R51") (pin "2") (pinfunction "2_2") (pintype "passive"))
    )
    (net (code "43") (name "D40") (class "Default")
      (node (ref "IC2") (pin "6") (pinfunction "QG_6") (pintype "tri_state"))
      (node (ref "R52") (pin "2") (pinfunction "2_2") (pintype "passive"))
    )
    (net (code "44") (name "D41") (class "Default")
      (node (ref "IC2") (pin "7") (pinfunction "QH_7") (pintype "tri_state"))
      (node (ref "R53") (pin "2") (pinfunction "2_2") (pintype "passive"))
    )
    (net (code "45") (name "D42") (class "Default")
      (node (ref "IC3") (pin "15") (pinfunction "QA_15") (pintype "tri_state"))
      (node (ref "R54") (pin "2") (pinfunction "2_2") (pintype "passive"))
    )
    (net (code "46") (name "D43") (class "Default")
      (node (ref "IC3") (pin "1") (pinfunction "QB_1") (pintype "tri_state"))
      (node (ref "R55") (pin "2") (pinfunction "2_2") (pintype "passive"))
    )
    (net (code "47") (name "D44") (class "Default")
      (node (ref "IC3") (pin "2") (pinfunction "QC_2") (pintype "tri_state"))
      (node (ref "R56") (pin "2") (pinfunction "2_2") (pintype "passive"))
    )
    (net (code "48") (name "D45") (class "Default")
      (node (ref "IC3") (pin "3") (pinfunction "QD_3") (pintype "tri_state"))
      (node (ref "R57") (pin "2") (pinfunction "2_2") (pintype "passive"))
    )
    (net (code "49") (name "D46") (class "Default")
      (node (ref "IC3") (pin "4") (pinfunction "QE_4") (pintype "tri_state"))
      (node (ref "R58") (pin "2") (pinfunction "2_2") (pintype "passive"))
    )
    (net (code "50") (name "DISP_D1") (class "Default")
      (node (ref "R3") (pin "1") (pinfunction "1_1") (pintype "passive"))
      (node (ref "U2") (pin "27") (pinfunction "PC4(ADC4/SDA)_27") (pintype "bidirectional"))
    )
    (net (code "51") (name "DISP_D2") (class "Default")
      (node (ref "R4") (pin "1") (pinfunction "1_1") (pintype "passive"))
      (node (ref "U2") (pin "28") (pinfunction "PC5(ADC5/SCL)_28") (pintype "bidirectional"))
    )
    (net (code "52") (name "DISP_D3") (class "Default")
      (node (ref "R5") (pin "1") (pinfunction "1_1") (pintype "passive"))
      (node (ref "U2") (pin "19") (pinfunction "ADC6_19") (pintype "bidirectional"))
    )
    (net (code "53") (name "DISP_D4") (class "Default")
      (node (ref "R13") (pin "1") (pinfunction "1_1") (pintype "passive"))
      (node (ref "U2") (pin "22") (pinfunction "ADC7_22") (pintype "bidirectional"))
    )
    (net (code "54") (name "DTR") (class "Default")
      (node (ref "C5") (pin "1") (pinfunction "1_1") (pintype "passive"))
      (node (ref "J2") (pin "6") (pinfunction "6_6") (pintype "bidirectional"))
    )
    (net (code "55") (name "GND") (class "Default")
      (node (ref "C1") (pin "C") (pinfunction "-_C") (pintype "passive"))
      (node (ref "C2") (pin "C") (pinfunction "-_C") (pintype "passive"))
      (node (ref "C3") (pin "2") (pinfunction "2_2") (pintype "passive"))
      (node (ref "C4") (pin "2") (pinfunction "2_2") (pintype "passive"))
      (node (ref "C6") (pin "2") (pinfunction "2_2") (pintype "passive"))
      (node (ref "D10") (pin "C") (pinfunction "C_C") (pintype "passive"))
      (node (ref "D11") (pin "C") (pinfunction "C_C") (pintype "passive"))
      (node (ref "D12") (pin "C") (pinfunction "C_C") (pintype "passive"))
      (node (ref "D13") (pin "C") (pinfunction "C_C") (pintype "passive"))
      (node (ref "D14") (pin "C") (pinfunction "C_C") (pintype "passive"))
      (node (ref "D15") (pin "C") (pinfunction "C_C") (pintype "passive"))
      (node (ref "D16") (pin "C") (pinfunction "C_C") (pintype "passive"))
      (node (ref "D17") (pin "C") (pinfunction "C_C") (pintype "passive"))
      (node (ref "D18") (pin "C") (pinfunction "C_C") (pintype "passive"))
      (node (ref "D19") (pin "C") (pinfunction "C_C") (pintype "passive"))
      (node (ref "D2") (pin "C") (pinfunction "C_C") (pintype "passive"))
      (node (ref "D20") (pin "C") (pinfunction "C_C") (pintype "passive"))
      (node (ref "D21") (pin "C") (pinfunction "C_C") (pintype "passive"))
      (node (ref "D22") (pin "C") (pinfunction "C_C") (pintype "passive"))
      (node (ref "D23") (pin "C") (pinfunction "C_C") (pintype "passive"))
      (node (ref "D24") (pin "C") (pinfunction "C_C") (pintype "passive"))
      (node (ref "D25") (pin "C") (pinfunction "C_C") (pintype "passive"))
      (node (ref "D26") (pin "C") (pinfunction "C_C") (pintype "passive"))
      (node (ref "D27") (pin "C") (pinfunction "C_C") (pintype "passive"))
      (node (ref "D28") (pin "C") (pinfunction "C_C") (pintype "passive"))
      (node (ref "D29") (pin "C") (pinfunction "C_C") (pintype "passive"))
      (node (ref "D3") (pin "C") (pinfunction "C_C") (pintype "passive"))
      (node (ref "D30") (pin "C") (pinfunction "C_C") (pintype "passive"))
      (node (ref "D31") (pin "C") (pinfunction "C_C") (pintype "passive"))
      (node (ref "D32") (pin "C") (pinfunction "C_C") (pintype "passive"))
      (node (ref "D33") (pin "C") (pinfunction "C_C") (pintype "passive"))
      (node (ref "D34") (pin "C") (pinfunction "C_C") (pintype "passive"))
      (node (ref "D35") (pin "C") (pinfunction "C_C") (pintype "passive"))
      (node (ref "D36") (pin "C") (pinfunction "C_C") (pintype "passive"))
      (node (ref "D37") (pin "C") (pinfunction "C_C") (pintype "passive"))
      (node (ref "D38") (pin "C") (pinfunction "C_C") (pintype "passive"))
      (node (ref "D39") (pin "C") (pinfunction "C_C") (pintype "passive"))
      (node (ref "D4") (pin "C") (pinfunction "C_C") (pintype "passive"))
      (node (ref "D40") (pin "C") (pinfunction "C_C") (pintype "passive"))
      (node (ref "D41") (pin "C") (pinfunction "C_C") (pintype "passive"))
      (node (ref "D42") (pin "C") (pinfunction "C_C") (pintype "passive"))
      (node (ref "D43") (pin "C") (pinfunction "C_C") (pintype "passive"))
      (node (ref "D44") (pin "C") (pinfunction "C_C") (pintype "passive"))
      (node (ref "D45") (pin "C") (pinfunction "C_C") (pintype "passive"))
      (node (ref "D46") (pin "C") (pinfunction "C_C") (pintype "passive"))
      (node (ref "D5") (pin "C") (pinfunction "C_C") (pintype "passive"))
      (node (ref "D6") (pin "C") (pinfunction "C_C") (pintype "passive"))
      (node (ref "D7") (pin "C") (pinfunction "C_C") (pintype "passive"))
      (node (ref "D8") (pin "C") (pinfunction "C_C") (pintype "passive"))
      (node (ref "D9") (pin "C") (pinfunction "C_C") (pintype "passive"))
      (node (ref "IC1") (pin "5") (pinfunction "LE_5") (pintype "input"))
      (node (ref "IC2") (pin "13") (pinfunction "G_13") (pintype "input"))
      (node (ref "IC3") (pin "13") (pinfunction "G_13") (pintype "input"))
      (node (ref "IC4") (pin "13") (pinfunction "G_13") (pintype "input"))
      (node (ref "IC5") (pin "13") (pinfunction "G_13") (pintype "input"))
      (node (ref "IC6") (pin "13") (pinfunction "G_13") (pintype "input"))
      (node (ref "IC7") (pin "13") (pinfunction "G_13") (pintype "input"))
      (node (ref "J1") (pin "1") (pinfunction "1_1") (pintype "passive"))
      (node (ref "J2") (pin "1") (pinfunction "1_1") (pintype "bidirectional"))
      (node (ref "R1") (pin "1") (pinfunction "1_1") (pintype "passive"))
      (node (ref "S1") (pin "2") (pinfunction "2_2") (pintype "passive"))
      (node (ref "U1") (pin "2") (pinfunction "GND_2") (pintype "input"))
      (node (ref "U2") (pin "21") (pinfunction "AGND_21") (pintype "bidirectional"))
      (node (ref "U2") (pin "3") (pinfunction "GND_3") (pintype "bidirectional"))
      (node (ref "U2") (pin "5") (pinfunction "GND_5") (pintype "bidirectional"))
      (node (ref "Y1") (pin "2") (pinfunction "2_2") (pintype "passive"))
    )
    (net (code "56") (name "LED_RCK") (class "Default")
      (node (ref "IC2") (pin "12") (pinfunction "RCK_12") (pintype "input"))
      (node (ref "IC3") (pin "12") (pinfunction "RCK_12") (pintype "input"))
      (node (ref "IC4") (pin "12") (pinfunction "RCK_12") (pintype "input"))
      (node (ref "IC5") (pin "12") (pinfunction "RCK_12") (pintype "input"))
      (node (ref "IC6") (pin "12") (pinfunction "RCK_12") (pintype "input"))
      (node (ref "IC7") (pin "12") (pinfunction "RCK_12") (pintype "input"))
      (node (ref "U2") (pin "12") (pinfunction "PB0(ICP)_12") (pintype "bidirectional"))
    )
    (net (code "57") (name "LED_SCK") (class "Default")
      (node (ref "IC2") (pin "11") (pinfunction "SCK_11") (pintype "input"))
      (node (ref "IC3") (pin "11") (pinfunction "SCK_11") (pintype "input"))
      (node (ref "IC4") (pin "11") (pinfunction "SCK_11") (pintype "input"))
      (node (ref "IC5") (pin "11") (pinfunction "SCK_11") (pintype "input"))
      (node (ref "IC6") (pin "11") (pinfunction "SCK_11") (pintype "input"))
      (node (ref "IC7") (pin "11") (pinfunction "SCK_11") (pintype "input"))
      (node (ref "U2") (pin "11") (pinfunction "PD7(AIN1)_11") (pintype "bidirectional"))
    )
    (net (code "58") (name "LED_SERIAL") (class "Default")
      (node (ref "IC4") (pin "14") (pinfunction "SER_14") (pintype "input"))
      (node (ref "U2") (pin "2") (pinfunction "PD4(XCK/T0)_2") (pintype "bidirectional"))
    )
    (net (code "59") (name "Net-(C1-+)") (class "Default")
      (node (ref "C1") (pin "A") (pinfunction "+_A") (pintype "passive"))
      (node (ref "J1") (pin "2") (pinfunction "2_2") (pintype "passive"))
      (node (ref "U1") (pin "1") (pinfunction "IN_1") (pintype "input"))
      (node (ref "U1") (pin "3") (pinfunction "EN_3") (pintype "input"))
    )
    (net (code "60") (name "Net-(D1-PadC)") (class "Default")
      (node (ref "D1") (pin "C") (pinfunction "C_C") (pintype "passive"))
      (node (ref "R1") (pin "2") (pinfunction "2_2") (pintype "passive"))
    )
    (net (code "61") (name "Net-(D2-PadA)") (class "Default")
      (node (ref "D2") (pin "A") (pinfunction "A_A") (pintype "passive"))
      (node (ref "R14") (pin "1") (pinfunction "1_1") (pintype "passive"))
    )
    (net (code "62") (name "Net-(D3-PadA)") (class "Default")
      (node (ref "D3") (pin "A") (pinfunction "A_A") (pintype "passive"))
      (node (ref "R15") (pin "1") (pinfunction "1_1") (pintype "passive"))
    )
    (net (code "63") (name "Net-(D4-PadA)") (class "Default")
      (node (ref "D4") (pin "A") (pinfunction "A_A") (pintype "passive"))
      (node (ref "R16") (pin "1") (pinfunction "1_1") (pintype "passive"))
    )
    (net (code "64") (name "Net-(D5-PadA)") (class "Default")
      (node (ref "D5") (pin "A") (pinfunction "A_A") (pintype "passive"))
      (node (ref "R17") (pin "1") (pinfunction "1_1") (pintype "passive"))
    )
    (net (code "65") (name "Net-(D6-PadA)") (class "Default")
      (node (ref "D6") (pin "A") (pinfunction "A_A") (pintype "passive"))
      (node (ref "R18") (pin "1") (pinfunction "1_1") (pintype "passive"))
    )
    (net (code "66") (name "Net-(D7-PadA)") (class "Default")
      (node (ref "D7") (pin "A") (pinfunction "A_A") (pintype "passive"))
      (node (ref "R19") (pin "1") (pinfunction "1_1") (pintype "passive"))
    )
    (net (code "67") (name "Net-(D8-PadA)") (class "Default")
      (node (ref "D8") (pin "A") (pinfunction "A_A") (pintype "passive"))
      (node (ref "R20") (pin "1") (pinfunction "1_1") (pintype "passive"))
    )
    (net (code "68") (name "Net-(D9-PadA)") (class "Default")
      (node (ref "D9") (pin "A") (pinfunction "A_A") (pintype "passive"))
      (node (ref "R21") (pin "1") (pinfunction "1_1") (pintype "passive"))
    )
    (net (code "69") (name "Net-(D10-PadA)") (class "Default")
      (node (ref "D10") (pin "A") (pinfunction "A_A") (pintype "passive"))
      (node (ref "R22") (pin "1") (pinfunction "1_1") (pintype "passive"))
    )
    (net (code "70") (name "Net-(D11-PadA)") (class "Default")
      (node (ref "D11") (pin "A") (pinfunction "A_A") (pintype "passive"))
      (node (ref "R23") (pin "1") (pinfunction "1_1") (pintype "passive"))
    )
    (net (code "71") (name "Net-(D12-PadA)") (class "Default")
      (node (ref "D12") (pin "A") (pinfunction "A_A") (pintype "passive"))
      (node (ref "R24") (pin "1") (pinfunction "1_1") (pintype "passive"))
    )
    (net (code "72") (name "Net-(D13-PadA)") (class "Default")
      (node (ref "D13") (pin "A") (pinfunction "A_A") (pintype "passive"))
      (node (ref "R25") (pin "1") (pinfunction "1_1") (pintype "passive"))
    )
    (net (code "73") (name "Net-(D14-PadA)") (class "Default")
      (node (ref "D14") (pin "A") (pinfunction "A_A") (pintype "passive"))
      (node (ref "R26") (pin "1") (pinfunction "1_1") (pintype "passive"))
    )
    (net (code "74") (name "Net-(D15-PadA)") (class "Default")
      (node (ref "D15") (pin "A") (pinfunction "A_A") (pintype "passive"))
      (node (ref "R27") (pin "1") (pinfunction "1_1") (pintype "passive"))
    )
    (net (code "75") (name "Net-(D16-PadA)") (class "Default")
      (node (ref "D16") (pin "A") (pinfunction "A_A") (pintype "passive"))
      (node (ref "R28") (pin "1") (pinfunction "1_1") (pintype "passive"))
    )
    (net (code "76") (name "Net-(D17-PadA)") (class "Default")
      (node (ref "D17") (pin "A") (pinfunction "A_A") (pintype "passive"))
      (node (ref "R29") (pin "1") (pinfunction "1_1") (pintype "passive"))
    )
    (net (code "77") (name "Net-(D18-PadA)") (class "Default")
      (node (ref "D18") (pin "A") (pinfunction "A_A") (pintype "passive"))
      (node (ref "R30") (pin "1") (pinfunction "1_1") (pintype "passive"))
    )
    (net (code "78") (name "Net-(D19-PadA)") (class "Default")
      (node (ref "D19") (pin "A") (pinfunction "A_A") (pintype "passive"))
      (node (ref "R31") (pin "1") (pinfunction "1_1") (pintype "passive"))
    )
    (net (code "79") (name "Net-(D20-PadA)") (class "Default")
      (node (ref "D20") (pin "A") (pinfunction "A_A") (pintype "passive"))
      (node (ref "R32") (pin "1") (pinfunction "1_1") (pintype "passive"))
    )
    (net (code "80") (name "Net-(D21-PadA)") (class "Default")
      (node (ref "D21") (pin "A") (pinfunction "A_A") (pintype "passive"))
      (node (ref "R33") (pin "1") (pinfunction "1_1") (pintype "passive"))
    )
    (net (code "81") (name "Net-(D22-PadA)") (class "Default")
      (node (ref "D22") (pin "A") (pinfunction "A_A") (pintype "passive"))
      (node (ref "R34") (pin "1") (pinfunction "1_1") (pintype "passive"))
    )
    (net (code "82") (name "Net-(D23-PadA)") (class "Default")
      (node (ref "D23") (pin "A") (pinfunction "A_A") (pintype "passive"))
      (node (ref "R35") (pin "1") (pinfunction "1_1") (pintype "passive"))
    )
    (net (code "83") (name "Net-(D24-PadA)") (class "Default")
      (node (ref "D24") (pin "A") (pinfunction "A_A") (pintype "passive"))
      (node (ref "R36") (pin "1") (pinfunction "1_1") (pintype "passive"))
    )
    (net (code "84") (name "Net-(D25-PadA)") (class "Default")
      (node (ref "D25") (pin "A") (pinfunction "A_A") (pintype "passive"))
      (node (ref "R37") (pin "1") (pinfunction "1_1") (pintype "passive"))
    )
    (net (code "85") (name "Net-(D26-PadA)") (class "Default")
      (node (ref "D26") (pin "A") (pinfunction "A_A") (pintype "passive"))
      (node (ref "R38") (pin "1") (pinfunction "1_1") (pintype "passive"))
    )
    (net (code "86") (name "Net-(D27-PadA)") (class "Default")
      (node (ref "D27") (pin "A") (pinfunction "A_A") (pintype "passive"))
      (node (ref "R39") (pin "1") (pinfunction "1_1") (pintype "passive"))
    )
    (net (code "87") (name "Net-(D28-PadA)") (class "Default")
      (node (ref "D28") (pin "A") (pinfunction "A_A") (pintype "passive"))
      (node (ref "R40") (pin "1") (pinfunction "1_1") (pintype "passive"))
    )
    (net (code "88") (name "Net-(D29-PadA)") (class "Default")
      (node (ref "D29") (pin "A") (pinfunction "A_A") (pintype "passive"))
      (node (ref "R41") (pin "1") (pinfunction "1_1") (pintype "passive"))
    )
    (net (code "89") (name "Net-(D30-PadA)") (class "Default")
      (node (ref "D30") (pin "A") (pinfunction "A_A") (pintype "passive"))
      (node (ref "R42") (pin "1") (pinfunction "1_1") (pintype "passive"))
    )
    (net (code "90") (name "Net-(D31-PadA)") (class "Default")
      (node (ref "D31") (pin "A") (pinfunction "A_A") (pintype "passive"))
      (node (ref "R43") (pin "1") (pinfunction "1_1") (pintype "passive"))
    )
    (net (code "91") (name "Net-(D32-PadA)") (class "Default")
      (node (ref "D32") (pin "A") (pinfunction "A_A") (pintype "passive"))
      (node (ref "R44") (pin "1") (pinfunction "1_1") (pintype "passive"))
    )
    (net (code "92") (name "Net-(D33-PadA)") (class "Default")
      (node (ref "D33") (pin "A") (pinfunction "A_A") (pintype "passive"))
      (node (ref "R45") (pin "1") (pinfunction "1_1") (pintype "passive"))
    )
    (net (code "93") (name "Net-(D34-PadA)") (class "Default")
      (node (ref "D34") (pin "A") (pinfunction "A_A") (pintype "passive"))
      (node (ref "R46") (pin "1") (pinfunction "1_1") (pintype "passive"))
    )
    (net (code "94") (name "Net-(D35-PadA)") (class "Default")
      (node (ref "D35") (pin "A") (pinfunction "A_A") (pintype "passive"))
      (node (ref "R47") (pin "1") (pinfunction "1_1") (pintype "passive"))
    )
    (net (code "95") (name "Net-(D36-PadA)") (class "Default")
      (node (ref "D36") (pin "A") (pinfunction "A_A") (pintype "passive"))
      (node (ref "R48") (pin "1") (pinfunction "1_1") (pintype "passive"))
    )
    (net (code "96") (name "Net-(D37-PadA)") (class "Default")
      (node (ref "D37") (pin "A") (pinfunction "A_A") (pintype "passive"))
      (node (ref "R49") (pin "1") (pinfunction "1_1") (pintype "passive"))
    )
    (net (code "97") (name "Net-(D38-PadA)") (class "Default")
      (node (ref "D38") (pin "A") (pinfunction "A_A") (pintype "passive"))
      (node (ref "R50") (pin "1") (pinfunction "1_1") (pintype "passive"))
    )
    (net (code "98") (name "Net-(D39-PadA)") (class "Default")
      (node (ref "D39") (pin "A") (pinfunction "A_A") (pintype "passive"))
      (node (ref "R51") (pin "1") (pinfunction "1_1") (pintype "passive"))
    )
    (net (code "99") (name "Net-(D40-PadA)") (class "Default")
      (node (ref "D40") (pin "A") (pinfunction "A_A") (pintype "passive"))
      (node (ref "R52") (pin "1") (pinfunction "1_1") (pintype "passive"))
    )
    (net (code "100") (name "Net-(D41-PadA)") (class "Default")
      (node (ref "D41") (pin "A") (pinfunction "A_A") (pintype "passive"))
      (node (ref "R53") (pin "1") (pinfunction "1_1") (pintype "passive"))
    )
    (net (code "101") (name "Net-(D42-PadA)") (class "Default")
      (node (ref "D42") (pin "A") (pinfunction "A_A") (pintype "passive"))
      (node (ref "R54") (pin "1") (pinfunction "1_1") (pintype "passive"))
    )
    (net (code "102") (name "Net-(D43-PadA)") (class "Default")
      (node (ref "D43") (pin "A") (pinfunction "A_A") (pintype "passive"))
      (node (ref "R55") (pin "1") (pinfunction "1_1") (pintype "passive"))
    )
    (net (code "103") (name "Net-(D44-PadA)") (class "Default")
      (node (ref "D44") (pin "A") (pinfunction "A_A") (pintype "passive"))
      (node (ref "R56") (pin "1") (pinfunction "1_1") (pintype "passive"))
    )
    (net (code "104") (name "Net-(D45-PadA)") (class "Default")
      (node (ref "D45") (pin "A") (pinfunction "A_A") (pintype "passive"))
      (node (ref "R57") (pin "1") (pinfunction "1_1") (pintype "passive"))
    )
    (net (code "105") (name "Net-(D46-PadA)") (class "Default")
      (node (ref "D46") (pin "A") (pinfunction "A_A") (pintype "passive"))
      (node (ref "R58") (pin "1") (pinfunction "1_1") (pintype "passive"))
    )
    (net (code "106") (name "Net-(IC1A-A)") (class "Default")
      (node (ref "IC1") (pin "13") (pinfunction "A_13") (pintype "output"))
      (node (ref "R6") (pin "1") (pinfunction "1_1") (pintype "passive"))
    )
    (net (code "107") (name "Net-(IC1A-B)") (class "Default")
      (node (ref "IC1") (pin "12") (pinfunction "B_12") (pintype "output"))
      (node (ref "R7") (pin "1") (pinfunction "1_1") (pintype "passive"))
    )
    (net (code "108") (name "Net-(IC1A-C)") (class "Default")
      (node (ref "IC1") (pin "11") (pinfunction "C_11") (pintype "output"))
      (node (ref "R8") (pin "1") (pinfunction "1_1") (pintype "passive"))
    )
    (net (code "109") (name "Net-(IC1A-D)") (class "Default")
      (node (ref "IC1") (pin "10") (pinfunction "D_10") (pintype "output"))
      (node (ref "R9") (pin "1") (pinfunction "1_1") (pintype "passive"))
    )
    (net (code "110") (name "Net-(IC1A-E)") (class "Default")
      (node (ref "IC1") (pin "9") (pinfunction "E_9") (pintype "output"))
      (node (ref "R10") (pin "1") (pinfunction "1_1") (pintype "passive"))
    )
    (net (code "111") (name "Net-(IC1A-F)") (class "Default")
      (node (ref "IC1") (pin "15") (pinfunction "F_15") (pintype "output"))
      (node (ref "R11") (pin "1") (pinfunction "1_1") (pintype "passive"))
    )
    (net (code "112") (name "Net-(IC1A-G)") (class "Default")
      (node (ref "IC1") (pin "14") (pinfunction "G_14") (pintype "output"))
      (node (ref "R12") (pin "1") (pinfunction "1_1") (pintype "passive"))
    )
    (net (code "113") (name "Net-(IC2A-QH*)") (class "Default")
      (node (ref "IC2") (pin "9") (pinfunction "QH*_9") (pintype "tri_state"))
      (node (ref "IC3") (pin "14") (pinfunction "SER_14") (pintype "input"))
    )
    (net (code "114") (name "Net-(IC4A-QH*)") (class "Default")
      (node (ref "IC4") (pin "9") (pinfunction "QH*_9") (pintype "tri_state"))
      (node (ref "IC5") (pin "14") (pinfunction "SER_14") (pintype "input"))
    )
    (net (code "115") (name "Net-(IC5A-QH*)") (class "Default")
      (node (ref "IC5") (pin "9") (pinfunction "QH*_9") (pintype "tri_state"))
      (node (ref "IC6") (pin "14") (pinfunction "SER_14") (pintype "input"))
    )
    (net (code "116") (name "Net-(IC6A-QH*)") (class "Default")
      (node (ref "IC6") (pin "9") (pinfunction "QH*_9") (pintype "tri_state"))
      (node (ref "IC7") (pin "14") (pinfunction "SER_14") (pintype "input"))
    )
    (net (code "117") (name "Net-(LED1-A)") (class "Default")
      (node (ref "LED1") (pin "14") (pinfunction "A_14") (pintype "bidirectional"))
      (node (ref "R6") (pin "2") (pinfunction "2_2") (pintype "passive"))
    )
    (net (code "118") (name "Net-(LED1-B)") (class "Default")
      (node (ref "LED1") (pin "16") (pinfunction "B_16") (pintype "bidirectional"))
      (node (ref "R7") (pin "2") (pinfunction "2_2") (pintype "passive"))
    )
    (net (code "119") (name "Net-(LED1-C)") (class "Default")
      (node (ref "LED1") (pin "13") (pinfunction "C_13") (pintype "bidirectional"))
      (node (ref "R8") (pin "2") (pinfunction "2_2") (pintype "passive"))
    )
    (net (code "120") (name "Net-(LED1-D)") (class "Default")
      (node (ref "LED1") (pin "3") (pinfunction "D_3") (pintype "bidirectional"))
      (node (ref "R9") (pin "2") (pinfunction "2_2") (pintype "passive"))
    )
    (net (code "121") (name "Net-(LED1-DIG1)") (class "Default")
      (node (ref "LED1") (pin "1") (pinfunction "DIG1_1") (pintype "bidirectional"))
      (node (ref "Q1") (pin "2") (pinfunction "E_2") (pintype "passive"))
    )
    (net (code "122") (name "Net-(LED1-DIG2)") (class "Default")
      (node (ref "LED1") (pin "2") (pinfunction "DIG2_2") (pintype "bidirectional"))
      (node (ref "Q2") (pin "2") (pinfunction "E_2") (pintype "passive"))
    )
    (net (code "123") (name "Net-(LED1-DIG3)") (class "Default")
      (node (ref "LED1") (pin "6") (pinfunction "DIG3_6") (pintype "bidirectional"))
      (node (ref "Q3") (pin "2") (pinfunction "E_2") (pintype "passive"))
    )
    (net (code "124") (name "Net-(LED1-DIG4)") (class "Default")
      (node (ref "LED1") (pin "8") (pinfunction "DIG4_8") (pintype "bidirectional"))
      (node (ref "Q4") (pin "2") (pinfunction "E_2") (pintype "passive"))
    )
    (net (code "125") (name "Net-(LED1-E)") (class "Default")
      (node (ref "LED1") (pin "5") (pinfunction "E_5") (pintype "bidirectional"))
      (node (ref "R10") (pin "2") (pinfunction "2_2") (pintype "passive"))
    )
    (net (code "126") (name "Net-(LED1-F)") (class "Default")
      (node (ref "LED1") (pin "11") (pinfunction "F_11") (pintype "bidirectional"))
      (node (ref "R11") (pin "2") (pinfunction "2_2") (pintype "passive"))
    )
    (net (code "127") (name "Net-(LED1-G)") (class "Default")
      (node (ref "LED1") (pin "15") (pinfunction "G_15") (pintype "bidirectional"))
      (node (ref "R12") (pin "2") (pinfunction "2_2") (pintype "passive"))
    )
    (net (code "128") (name "Net-(Q1-B)") (class "Default")
      (node (ref "Q1") (pin "1") (pinfunction "B_1") (pintype "passive"))
      (node (ref "R3") (pin "2") (pinfunction "2_2") (pintype "passive"))
    )
    (net (code "129") (name "Net-(Q2-B)") (class "Default")
      (node (ref "Q2") (pin "1") (pinfunction "B_1") (pintype "passive"))
      (node (ref "R4") (pin "2") (pinfunction "2_2") (pintype "passive"))
    )
    (net (code "130") (name "Net-(Q3-B)") (class "Default")
      (node (ref "Q3") (pin "1") (pinfunction "B_1") (pintype "passive"))
      (node (ref "R5") (pin "2") (pinfunction "2_2") (pintype "passive"))
    )
    (net (code "131") (name "Net-(Q4-B)") (class "Default")
      (node (ref "Q4") (pin "1") (pinfunction "B_1") (pintype "passive"))
      (node (ref "R13") (pin "2") (pinfunction "2_2") (pintype "passive"))
    )
    (net (code "132") (name "Net-(U2-AREF)") (class "Default")
      (node (ref "C6") (pin "1") (pinfunction "1_1") (pintype "passive"))
      (node (ref "U2") (pin "20") (pinfunction "AREF_20") (pintype "bidirectional"))
    )
    (net (code "133") (name "Net-(U2-PB6(XTAL1{slash}TOSC1))") (class "Default")
      (node (ref "U2") (pin "7") (pinfunction "PB6(XTAL1/TOSC1)_7") (pintype "bidirectional"))
      (node (ref "Y1") (pin "1") (pinfunction "1_1") (pintype "passive"))
    )
    (net (code "134") (name "Net-(U2-PB7(XTAL2{slash}TOSC2))") (class "Default")
      (node (ref "U2") (pin "8") (pinfunction "PB7(XTAL2/TOSC2)_8") (pintype "bidirectional"))
      (node (ref "Y1") (pin "3") (pinfunction "3_3") (pintype "passive"))
    )
    (net (code "135") (name "Net-(U2-PC6({slash}RESET))") (class "Default")
      (node (ref "C5") (pin "2") (pinfunction "2_2") (pintype "passive"))
      (node (ref "R2") (pin "1") (pinfunction "1_1") (pintype "passive"))
      (node (ref "S1") (pin "1") (pinfunction "1_1") (pintype "passive"))
      (node (ref "U2") (pin "29") (pinfunction "PC6(/RESET)_29") (pintype "bidirectional"))
    )
    (net (code "136") (name "OUT") (class "Default")
      (node (ref "IC2") (pin "14") (pinfunction "SER_14") (pintype "input"))
      (node (ref "IC7") (pin "9") (pinfunction "QH*_9") (pintype "tri_state"))
    )
    (net (code "137") (name "RX") (class "Default")
      (node (ref "J2") (pin "3") (pinfunction "3_3") (pintype "bidirectional"))
      (node (ref "U2") (pin "31") (pinfunction "PD1(TXD)_31") (pintype "bidirectional"))
    )
    (net (code "138") (name "TX") (class "Default")
      (node (ref "J2") (pin "4") (pinfunction "4_4") (pintype "bidirectional"))
      (node (ref "U2") (pin "30") (pinfunction "PD0(RXD)_30") (pintype "bidirectional"))
    )
    (net (code "139") (name "VCC") (class "Default")
      (node (ref "C2") (pin "A") (pinfunction "+_A") (pintype "passive"))
      (node (ref "C3") (pin "1") (pinfunction "1_1") (pintype "passive"))
      (node (ref "C4") (pin "1") (pinfunction "1_1") (pintype "passive"))
      (node (ref "D1") (pin "A") (pinfunction "A_A") (pintype "passive"))
      (node (ref "IC1") (pin "3") (pinfunction "LT_3") (pintype "input"))
      (node (ref "IC1") (pin "4") (pinfunction "BI_4") (pintype "input"))
      (node (ref "IC2") (pin "10") (pinfunction "SCL_10") (pintype "input"))
      (node (ref "IC3") (pin "10") (pinfunction "SCL_10") (pintype "input"))
      (node (ref "IC4") (pin "10") (pinfunction "SCL_10") (pintype "input"))
      (node (ref "IC5") (pin "10") (pinfunction "SCL_10") (pintype "input"))
      (node (ref "IC6") (pin "10") (pinfunction "SCL_10") (pintype "input"))
      (node (ref "IC7") (pin "10") (pinfunction "SCL_10") (pintype "input"))
      (node (ref "J2") (pin "2") (pinfunction "2_2") (pintype "bidirectional"))
      (node (ref "Q1") (pin "3") (pinfunction "C_3") (pintype "passive"))
      (node (ref "Q2") (pin "3") (pinfunction "C_3") (pintype "passive"))
      (node (ref "Q3") (pin "3") (pinfunction "C_3") (pintype "passive"))
      (node (ref "Q4") (pin "3") (pinfunction "C_3") (pintype "passive"))
      (node (ref "R2") (pin "2") (pinfunction "2_2") (pintype "passive"))
      (node (ref "U1") (pin "5") (pinfunction "OUT_5") (pintype "passive"))
      (node (ref "U2") (pin "18") (pinfunction "AVCC_18") (pintype "bidirectional"))
      (node (ref "U2") (pin "4") (pinfunction "VCC_4") (pintype "bidirectional"))
      (node (ref "U2") (pin "6") (pinfunction "VCC_6") (pintype "bidirectional"))
    )
    (net (code "140") (name "unconnected-(IC3A-QF-Pad5)") (class "Default")
      (node (ref "IC3") (pin "5") (pinfunction "QF_5") (pintype "tri_state"))
    )
    (net (code "141") (name "unconnected-(IC3A-QG-Pad6)") (class "Default")
      (node (ref "IC3") (pin "6") (pinfunction "QG_6") (pintype "tri_state"))
    )
    (net (code "142") (name "unconnected-(IC3A-QH*-Pad9)") (class "Default")
      (node (ref "IC3") (pin "9") (pinfunction "QH*_9") (pintype "tri_state"))
    )
    (net (code "143") (name "unconnected-(IC3A-QH-Pad7)") (class "Default")
      (node (ref "IC3") (pin "7") (pinfunction "QH_7") (pintype "tri_state"))
    )
    (net (code "144") (name "unconnected-(J2-Pad5)") (class "Default")
      (node (ref "J2") (pin "5") (pinfunction "5_5") (pintype "bidirectional"))
    )
    (net (code "145") (name "unconnected-(LED1-APOS-A-Pad10)") (class "Default")
      (node (ref "LED1") (pin "10") (pinfunction "APOS-A_10") (pintype "bidirectional"))
    )
    (net (code "146") (name "unconnected-(LED1-APOS-C-Pad9)") (class "Default")
      (node (ref "LED1") (pin "9") (pinfunction "APOS-C_9") (pintype "bidirectional"))
    )
    (net (code "147") (name "unconnected-(LED1-COL-A-Pad4)") (class "Default")
      (node (ref "LED1") (pin "4") (pinfunction "COL-A_4") (pintype "bidirectional"))
    )
    (net (code "148") (name "unconnected-(LED1-COL-C-Pad12)") (class "Default")
      (node (ref "LED1") (pin "12") (pinfunction "COL-C_12") (pintype "bidirectional"))
    )
    (net (code "149") (name "unconnected-(LED1-DP-Pad7)") (class "Default")
      (node (ref "LED1") (pin "7") (pinfunction "DP_7") (pintype "bidirectional"))
    )
    (net (code "150") (name "unconnected-(U1-BP-Pad4)") (class "Default")
      (node (ref "U1") (pin "4") (pinfunction "BP_4") (pintype "input"))
    )
    (net (code "151") (name "unconnected-(U2-PB1(OC1A)-Pad13)") (class "Default")
      (node (ref "U2") (pin "13") (pinfunction "PB1(OC1A)_13") (pintype "bidirectional"))
    )
    (net (code "152") (name "unconnected-(U2-PB2(SS{slash}OC1B)-Pad14)") (class "Default")
      (node (ref "U2") (pin "14") (pinfunction "PB2(SS/OC1B)_14") (pintype "bidirectional"))
    )
    (net (code "153") (name "unconnected-(U2-PB3(MOSI{slash}OC2)-Pad15)") (class "Default")
      (node (ref "U2") (pin "15") (pinfunction "PB3(MOSI/OC2)_15") (pintype "bidirectional"))
    )
    (net (code "154") (name "unconnected-(U2-PB4(MISO)-Pad16)") (class "Default")
      (node (ref "U2") (pin "16") (pinfunction "PB4(MISO)_16") (pintype "bidirectional"))
    )
    (net (code "155") (name "unconnected-(U2-PB5(SCK)-Pad17)") (class "Default")
      (node (ref "U2") (pin "17") (pinfunction "PB5(SCK)_17") (pintype "bidirectional"))
    )
    (net (code "156") (name "unconnected-(U2-PD2(INT0)-Pad32)") (class "Default")
      (node (ref "U2") (pin "32") (pinfunction "PD2(INT0)_32") (pintype "bidirectional"))
    )
    (net (code "157") (name "unconnected-(U2-PD3(INT1)-Pad1)") (class "Default")
      (node (ref "U2") (pin "1") (pinfunction "PD3(INT1)_1") (pintype "bidirectional"))
    )
    (net (code "158") (name "unconnected-(U2-PD5(T1)-Pad9)") (class "Default")
      (node (ref "U2") (pin "9") (pinfunction "PD5(T1)_9") (pintype "bidirectional"))
    )
    (net (code "159") (name "unconnected-(U2-PD6(AIN0)-Pad10)") (class "Default")
      (node (ref "U2") (pin "10") (pinfunction "PD6(AIN0)_10") (pintype "bidirectional"))
    )
  )
)
